# SteppyMk2_10x10.net
KiCad netlist of a schematic drawn in EAGLE
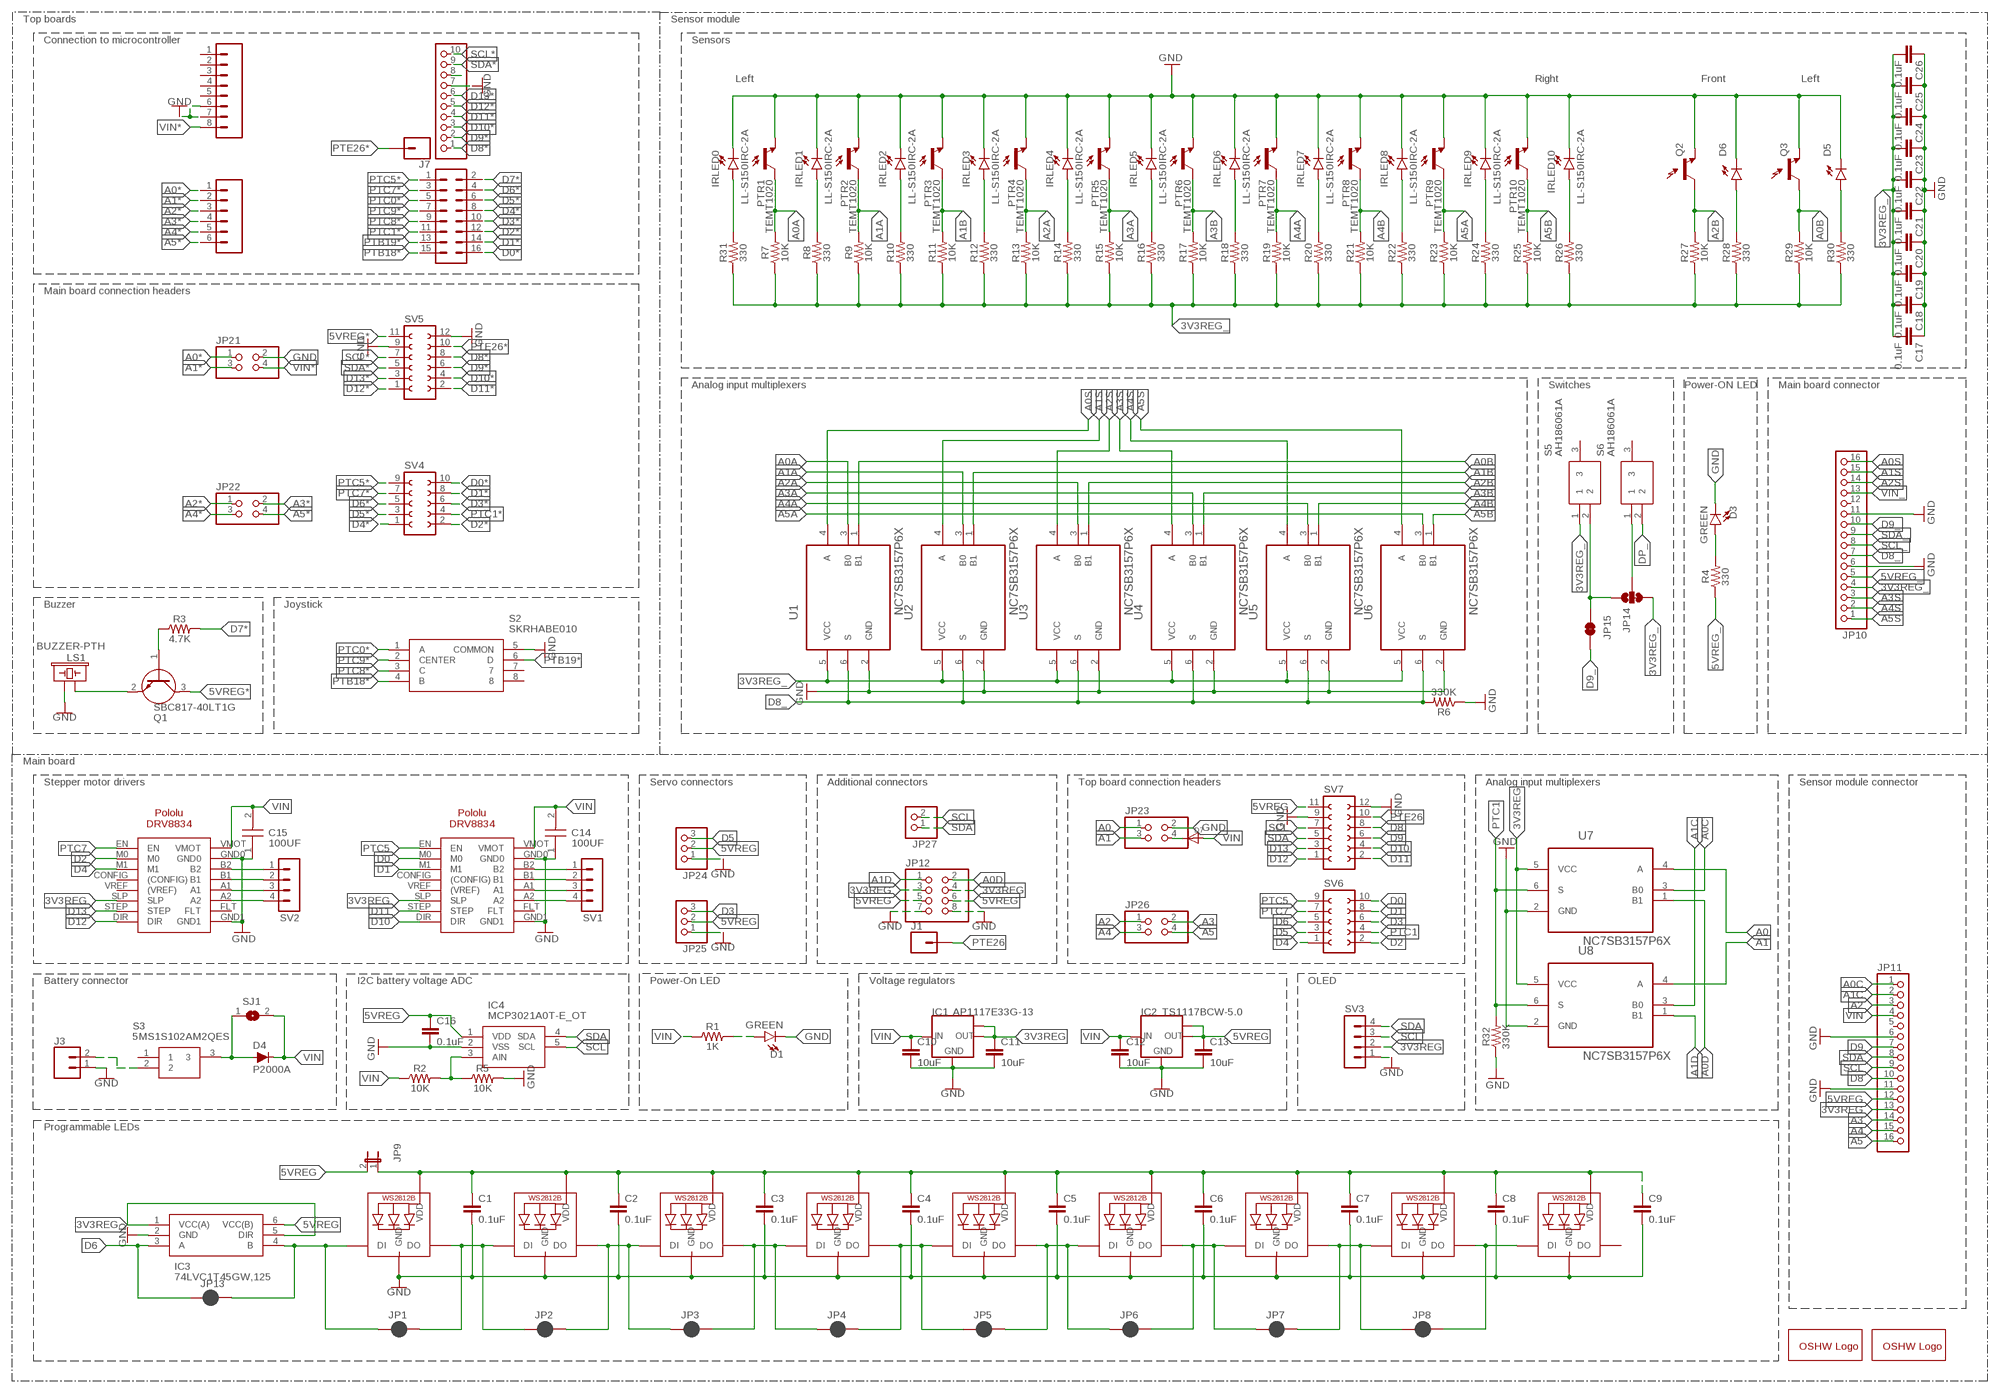
[diagram p0: schematic, sheet 1]

(export (version "E")
  (design (tool "Eeschema 10.0.6"))
  (components
    (comp (ref "C1")
      (value "0.1uF")
      (footprint "eagle-import:0603")
      (libsource (lib "eagle-import") (part "0.1UF-0603-25V-5%"))
    )
    (comp (ref "C2")
      (value "0.1uF")
      (footprint "eagle-import:0603")
      (libsource (lib "eagle-import") (part "0.1UF-0603-25V-5%"))
    )
    (comp (ref "C3")
      (value "0.1uF")
      (footprint "eagle-import:0603")
      (libsource (lib "eagle-import") (part "0.1UF-0603-25V-5%"))
    )
    (comp (ref "C4")
      (value "0.1uF")
      (footprint "eagle-import:0603")
      (libsource (lib "eagle-import") (part "0.1UF-0603-25V-5%"))
    )
    (comp (ref "C5")
      (value "0.1uF")
      (footprint "eagle-import:0603")
      (libsource (lib "eagle-import") (part "0.1UF-0603-25V-5%"))
    )
    (comp (ref "C6")
      (value "0.1uF")
      (footprint "eagle-import:0603")
      (libsource (lib "eagle-import") (part "0.1UF-0603-25V-5%"))
    )
    (comp (ref "C7")
      (value "0.1uF")
      (footprint "eagle-import:0603")
      (libsource (lib "eagle-import") (part "0.1UF-0603-25V-5%"))
    )
    (comp (ref "C8")
      (value "0.1uF")
      (footprint "eagle-import:0603")
      (libsource (lib "eagle-import") (part "0.1UF-0603-25V-5%"))
    )
    (comp (ref "C9")
      (value "0.1uF")
      (footprint "eagle-import:0603")
      (libsource (lib "eagle-import") (part "0.1UF-0603-25V-5%"))
    )
    (comp (ref "C10")
      (value "10uF")
      (footprint "eagle-import:0805")
      (libsource (lib "eagle-import") (part "10UF-0805-10V-10%"))
    )
    (comp (ref "C11")
      (value "10uF")
      (footprint "eagle-import:0805")
      (libsource (lib "eagle-import") (part "10UF-0805-10V-10%"))
    )
    (comp (ref "C12")
      (value "10uF")
      (footprint "eagle-import:0805")
      (libsource (lib "eagle-import") (part "10UF-0805-10V-10%"))
    )
    (comp (ref "C13")
      (value "10uF")
      (footprint "eagle-import:0805")
      (libsource (lib "eagle-import") (part "10UF-0805-10V-10%"))
    )
    (comp (ref "C14")
      (value "100UF")
      (footprint "eagle-import:CAPM7058X610N")
      (fields
        (field (name "MANUFACTURER_PART_NUMBER") "EEEFK1C101P")
        (field (name "RS_PART_NUMBER") "5370433P")
      )
      (libsource (lib "eagle-import") (part "EEEFK1C101P"))
    )
    (comp (ref "C15")
      (value "100UF")
      (footprint "eagle-import:CAPM7058X610N")
      (fields
        (field (name "MANUFACTURER_PART_NUMBER") "EEEFK1C101P")
        (field (name "RS_PART_NUMBER") "5370433P")
      )
      (libsource (lib "eagle-import") (part "EEEFK1C101P"))
    )
    (comp (ref "C16")
      (value "0.1uF")
      (footprint "eagle-import:0603")
      (libsource (lib "eagle-import") (part "0.1UF-0603-25V-5%"))
    )
    (comp (ref "C17")
      (value "0.1uF")
      (footprint "eagle-import:0603")
      (libsource (lib "eagle-import") (part "0.1UF-0603-25V-5%"))
    )
    (comp (ref "C18")
      (value "0.1uF")
      (footprint "eagle-import:0603")
      (libsource (lib "eagle-import") (part "0.1UF-0603-25V-5%"))
    )
    (comp (ref "C19")
      (value "0.1uF")
      (footprint "eagle-import:0603")
      (libsource (lib "eagle-import") (part "0.1UF-0603-25V-5%"))
    )
    (comp (ref "C20")
      (value "0.1uF")
      (footprint "eagle-import:0603")
      (libsource (lib "eagle-import") (part "0.1UF-0603-25V-5%"))
    )
    (comp (ref "C21")
      (value "0.1uF")
      (footprint "eagle-import:0603")
      (libsource (lib "eagle-import") (part "0.1UF-0603-25V-5%"))
    )
    (comp (ref "C22")
      (value "0.1uF")
      (footprint "eagle-import:0603")
      (libsource (lib "eagle-import") (part "0.1UF-0603-25V-5%"))
    )
    (comp (ref "C23")
      (value "0.1uF")
      (footprint "eagle-import:0603")
      (libsource (lib "eagle-import") (part "0.1UF-0603-25V-5%"))
    )
    (comp (ref "C24")
      (value "0.1uF")
      (footprint "eagle-import:0603")
      (libsource (lib "eagle-import") (part "0.1UF-0603-25V-5%"))
    )
    (comp (ref "C25")
      (value "0.1uF")
      (footprint "eagle-import:0603")
      (libsource (lib "eagle-import") (part "0.1UF-0603-25V-5%"))
    )
    (comp (ref "C26")
      (value "0.1uF")
      (footprint "eagle-import:0603")
      (libsource (lib "eagle-import") (part "0.1UF-0603-25V-5%"))
    )
    (comp (ref "CONLEFT")
      (value "POLOLU-DRV8825")
      (footprint "eagle-import:POLOLU-DRV8825")
      (libsource (lib "eagle-import") (part "POLOLU-DRV8825"))
    )
    (comp (ref "D1")
      (value "GREEN")
      (footprint "eagle-import:LED-1206")
      (libsource (lib "eagle-import") (part "LED-GREEN1206"))
    )
    (comp (ref "D3")
      (value "GREEN")
      (footprint "eagle-import:LED-1206")
      (libsource (lib "eagle-import") (part "LED-GREEN1206"))
    )
    (comp (ref "D4")
      (value "P2000A")
      (footprint "eagle-import:DIODE-1N4001")
      (libsource (lib "eagle-import") (part "DIODE-PTH"))
    )
    (comp (ref "D5")
      (value "LED-IRSIDE_EMITTER")
      (footprint "eagle-import:LTE-302")
      (libsource (lib "eagle-import") (part "LED-IRSIDE_EMITTER"))
    )
    (comp (ref "D6")
      (value "LED-IRSIDE_EMITTER")
      (footprint "eagle-import:LTE-302")
      (libsource (lib "eagle-import") (part "LED-IRSIDE_EMITTER"))
    )
    (comp (ref "D7")
      (value "DIODESMA")
      (footprint "eagle-import:SMADIODE")
      (libsource (lib "eagle-import") (part "DIODESMA"))
    )
    (comp (ref "GOLD_ORB_SM1")
      (value "OSHWLOGOLOGO8MM")
      (footprint "eagle-import:OSHW_8MM")
      (libsource (lib "eagle-import") (part "OSHWLOGOLOGO8MM"))
    )
    (comp (ref "GOLD_ORB_SM2")
      (value "OSHWLOGOLOGO5MM")
      (footprint "eagle-import:OSHW_5MM")
      (libsource (lib "eagle-import") (part "OSHWLOGOLOGO5MM"))
    )
    (comp (ref "IC1")
      (value "AP1117E33G-13")
      (footprint "eagle-import:SOT223")
      (libsource (lib "eagle-import") (part "LM1117IMPX-3.3"))
    )
    (comp (ref "IC2")
      (value "TS1117BCW-5.0")
      (footprint "eagle-import:SOT223")
      (libsource (lib "eagle-import") (part "LM1117IMPX-5.0"))
    )
    (comp (ref "IC3")
      (value "74LVC1T45GW,125")
      (footprint "eagle-import:SOT65P210X110-6N")
      (fields
        (field (name "MOUSER_PART_NUMBER") "771-74LVC1T45GW125")
        (field (name "RS_PART_NUMBER") "8168791P")
      )
      (libsource (lib "eagle-import") (part "74LVC1T45GW,125"))
    )
    (comp (ref "IC4")
      (value "MCP3021A0T-E_OT")
      (footprint "eagle-import:SOT95P280X145-5N")
      (fields
        (field (name "MANUFACTURER_PART_NUMBER") "MCP3021A0T-E/OT")
        (field (name "MOUSER_PART_NUMBER") "579-MCP3021A0T-E/OT")
      )
      (libsource (lib "eagle-import") (part "MCP3021A0T-E_OT"))
    )
    (comp (ref "IRLED0")
      (value "LL-S150IRC-2A")
      (footprint "eagle-import:LEDC3215X130N")
      (fields
        (field (name "MANUFACTURER_PART_NUMBER") "PT15-21C/TR8")
        (field (name "MOUSER_PART_NUMBER") "638-PT1521CTR8")
      )
      (libsource (lib "eagle-import") (part "PT15-21C_TR8"))
    )
    (comp (ref "IRLED1")
      (value "LL-S150IRC-2A")
      (footprint "eagle-import:LEDC3215X130N")
      (fields
        (field (name "MANUFACTURER_PART_NUMBER") "PT15-21C/TR8")
        (field (name "MOUSER_PART_NUMBER") "638-PT1521CTR8")
      )
      (libsource (lib "eagle-import") (part "PT15-21C_TR8"))
    )
    (comp (ref "IRLED2")
      (value "LL-S150IRC-2A")
      (footprint "eagle-import:LEDC3215X130N")
      (fields
        (field (name "MANUFACTURER_PART_NUMBER") "PT15-21C/TR8")
        (field (name "MOUSER_PART_NUMBER") "638-PT1521CTR8")
      )
      (libsource (lib "eagle-import") (part "PT15-21C_TR8"))
    )
    (comp (ref "IRLED3")
      (value "LL-S150IRC-2A")
      (footprint "eagle-import:LEDC3215X130N")
      (fields
        (field (name "MANUFACTURER_PART_NUMBER") "PT15-21C/TR8")
        (field (name "MOUSER_PART_NUMBER") "638-PT1521CTR8")
      )
      (libsource (lib "eagle-import") (part "PT15-21C_TR8"))
    )
    (comp (ref "IRLED4")
      (value "LL-S150IRC-2A")
      (footprint "eagle-import:LEDC3215X130N")
      (fields
        (field (name "MANUFACTURER_PART_NUMBER") "PT15-21C/TR8")
        (field (name "MOUSER_PART_NUMBER") "638-PT1521CTR8")
      )
      (libsource (lib "eagle-import") (part "PT15-21C_TR8"))
    )
    (comp (ref "IRLED5")
      (value "LL-S150IRC-2A")
      (footprint "eagle-import:LEDC3215X130N")
      (fields
        (field (name "MANUFACTURER_PART_NUMBER") "PT15-21C/TR8")
        (field (name "MOUSER_PART_NUMBER") "638-PT1521CTR8")
      )
      (libsource (lib "eagle-import") (part "PT15-21C_TR8"))
    )
    (comp (ref "IRLED6")
      (value "LL-S150IRC-2A")
      (footprint "eagle-import:LEDC3215X130N")
      (fields
        (field (name "MANUFACTURER_PART_NUMBER") "PT15-21C/TR8")
        (field (name "MOUSER_PART_NUMBER") "638-PT1521CTR8")
      )
      (libsource (lib "eagle-import") (part "PT15-21C_TR8"))
    )
    (comp (ref "IRLED7")
      (value "LL-S150IRC-2A")
      (footprint "eagle-import:LEDC3215X130N")
      (fields
        (field (name "MANUFACTURER_PART_NUMBER") "PT15-21C/TR8")
        (field (name "MOUSER_PART_NUMBER") "638-PT1521CTR8")
      )
      (libsource (lib "eagle-import") (part "PT15-21C_TR8"))
    )
    (comp (ref "IRLED8")
      (value "LL-S150IRC-2A")
      (footprint "eagle-import:LEDC3215X130N")
      (fields
        (field (name "MANUFACTURER_PART_NUMBER") "PT15-21C/TR8")
        (field (name "MOUSER_PART_NUMBER") "638-PT1521CTR8")
      )
      (libsource (lib "eagle-import") (part "PT15-21C_TR8"))
    )
    (comp (ref "IRLED9")
      (value "LL-S150IRC-2A")
      (footprint "eagle-import:LEDC3215X130N")
      (fields
        (field (name "MANUFACTURER_PART_NUMBER") "PT15-21C/TR8")
        (field (name "MOUSER_PART_NUMBER") "638-PT1521CTR8")
      )
      (libsource (lib "eagle-import") (part "PT15-21C_TR8"))
    )
    (comp (ref "IRLED10")
      (value "LL-S150IRC-2A")
      (footprint "eagle-import:LEDC3215X130N")
      (fields
        (field (name "MANUFACTURER_PART_NUMBER") "PT15-21C/TR8")
        (field (name "MOUSER_PART_NUMBER") "638-PT1521CTR8")
      )
      (libsource (lib "eagle-import") (part "PT15-21C_TR8"))
    )
    (comp (ref "J1")
      (value "CONN_01")
      (footprint "eagle-import:1X01")
      (libsource (lib "eagle-import") (part "CONN_01"))
    )
    (comp (ref "J3")
      (value "CONN_02")
      (footprint "eagle-import:1X02")
      (libsource (lib "eagle-import") (part "CONN_02"))
    )
    (comp (ref "J5")
      (value "CONN_08\"")
      (footprint "eagle-import:1X08")
      (libsource (lib "eagle-import") (part "CONN_08{dblquote}"))
    )
    (comp (ref "J6")
      (value "CONN_06SILK_FEMALE_PTH")
      (footprint "eagle-import:1X06")
      (libsource (lib "eagle-import") (part "CONN_06SILK_FEMALE_PTH"))
    )
    (comp (ref "J7")
      (value "CONN_01")
      (footprint "eagle-import:1X01")
      (libsource (lib "eagle-import") (part "CONN_01"))
    )
    (comp (ref "J8")
      (value "CONN_08X2_HEADER")
      (footprint "eagle-import:2X8")
      (libsource (lib "eagle-import") (part "CONN_08X2_HEADER"))
    )
    (comp (ref "JP1")
      (value "JUMPER-SMT_2_NC_PASTE_SILK")
      (footprint "eagle-import:SMT-JUMPER_2_NC_PASTE_SILK")
      (libsource (lib "eagle-import") (part "JUMPER-SMT_2_NC_PASTE_SILK"))
    )
    (comp (ref "JP2")
      (value "JUMPER-SMT_2_NC_PASTE_SILK")
      (footprint "eagle-import:SMT-JUMPER_2_NC_PASTE_SILK")
      (libsource (lib "eagle-import") (part "JUMPER-SMT_2_NC_PASTE_SILK"))
    )
    (comp (ref "JP3")
      (value "JUMPER-SMT_2_NC_PASTE_SILK")
      (footprint "eagle-import:SMT-JUMPER_2_NC_PASTE_SILK")
      (libsource (lib "eagle-import") (part "JUMPER-SMT_2_NC_PASTE_SILK"))
    )
    (comp (ref "JP4")
      (value "JUMPER-SMT_2_NC_PASTE_SILK")
      (footprint "eagle-import:SMT-JUMPER_2_NC_PASTE_SILK")
      (libsource (lib "eagle-import") (part "JUMPER-SMT_2_NC_PASTE_SILK"))
    )
    (comp (ref "JP5")
      (value "JUMPER-SMT_2_NC_PASTE_SILK")
      (footprint "eagle-import:SMT-JUMPER_2_NC_PASTE_SILK")
      (libsource (lib "eagle-import") (part "JUMPER-SMT_2_NC_PASTE_SILK"))
    )
    (comp (ref "JP6")
      (value "JUMPER-SMT_2_NC_PASTE_SILK")
      (footprint "eagle-import:SMT-JUMPER_2_NC_PASTE_SILK")
      (libsource (lib "eagle-import") (part "JUMPER-SMT_2_NC_PASTE_SILK"))
    )
    (comp (ref "JP7")
      (value "JUMPER-SMT_2_NC_PASTE_SILK")
      (footprint "eagle-import:SMT-JUMPER_2_NC_PASTE_SILK")
      (libsource (lib "eagle-import") (part "JUMPER-SMT_2_NC_PASTE_SILK"))
    )
    (comp (ref "JP8")
      (value "JUMPER-SMT_2_NC_PASTE_SILK")
      (footprint "eagle-import:SMT-JUMPER_2_NC_PASTE_SILK")
      (libsource (lib "eagle-import") (part "JUMPER-SMT_2_NC_PASTE_SILK"))
    )
    (comp (ref "JP9")
      (value "JP1E")
      (footprint "eagle-import:JP1")
      (libsource (lib "eagle-import") (part "JP1E"))
    )
    (comp (ref "JP10")
      (value "PINHD-1X16/90")
      (footprint "eagle-import:1X16_90")
      (libsource (lib "eagle-import") (part "PINHD-1X16/90"))
    )
    (comp (ref "JP11")
      (value "PINHD-1X16")
      (footprint "eagle-import:1X16")
      (libsource (lib "eagle-import") (part "PINHD-1X16"))
    )
    (comp (ref "JP12")
      (value "PINHD-2X4")
      (footprint "eagle-import:2X04")
      (libsource (lib "eagle-import") (part "PINHD-2X4"))
    )
    (comp (ref "JP13")
      (value "JUMPER-SMT_2_NC_PASTE_SILK")
      (footprint "eagle-import:SMT-JUMPER_2_NC_PASTE_SILK")
      (libsource (lib "eagle-import") (part "JUMPER-SMT_2_NC_PASTE_SILK"))
    )
    (comp (ref "JP14")
      (value "JUMPER-SMT_3_1-NC_TRACE_SILK")
      (footprint "eagle-import:SMT-JUMPER_3_1-NC_TRACE_SILK")
      (libsource (lib "eagle-import") (part "JUMPER-SMT_3_1-NC_TRACE_SILK"))
    )
    (comp (ref "JP15")
      (value "JUMPER-SMT_2_NC_TRACE_SILK")
      (footprint "eagle-import:SMT-JUMPER_2_NC_TRACE_SILK")
      (libsource (lib "eagle-import") (part "JUMPER-SMT_2_NC_TRACE_SILK"))
    )
    (comp (ref "JP21")
      (value "PINHD-2X2")
      (footprint "eagle-import:2X02")
      (libsource (lib "eagle-import") (part "PINHD-2X2"))
    )
    (comp (ref "JP22")
      (value "PINHD-2X2")
      (footprint "eagle-import:2X02")
      (libsource (lib "eagle-import") (part "PINHD-2X2"))
    )
    (comp (ref "JP23")
      (value "PINHD-2X2")
      (footprint "eagle-import:2X02")
      (libsource (lib "eagle-import") (part "PINHD-2X2"))
    )
    (comp (ref "JP24")
      (value "PINHD-1X3")
      (footprint "eagle-import:1X03")
      (libsource (lib "eagle-import") (part "PINHD-1X3"))
    )
    (comp (ref "JP25")
      (value "PINHD-1X3")
      (footprint "eagle-import:1X03")
      (libsource (lib "eagle-import") (part "PINHD-1X3"))
    )
    (comp (ref "JP26")
      (value "PINHD-2X2")
      (footprint "eagle-import:2X02")
      (libsource (lib "eagle-import") (part "PINHD-2X2"))
    )
    (comp (ref "JP27")
      (value "PINHD-1X2")
      (footprint "eagle-import:1X02")
      (libsource (lib "eagle-import") (part "PINHD-1X2"))
    )
    (comp (ref "LED1")
      (value "WS2812B3535")
      (footprint "eagle-import:LED3535")
      (libsource (lib "eagle-import") (part "WS2812B3535"))
    )
    (comp (ref "LED2")
      (value "WS2812B3535")
      (footprint "eagle-import:LED3535")
      (libsource (lib "eagle-import") (part "WS2812B3535"))
    )
    (comp (ref "LED3")
      (value "WS2812B3535")
      (footprint "eagle-import:LED3535")
      (libsource (lib "eagle-import") (part "WS2812B3535"))
    )
    (comp (ref "LED4")
      (value "WS2812B3535")
      (footprint "eagle-import:LED3535")
      (libsource (lib "eagle-import") (part "WS2812B3535"))
    )
    (comp (ref "LED5")
      (value "WS2812B3535")
      (footprint "eagle-import:LED3535")
      (libsource (lib "eagle-import") (part "WS2812B3535"))
    )
    (comp (ref "LED6")
      (value "WS2812B3535")
      (footprint "eagle-import:LED3535")
      (libsource (lib "eagle-import") (part "WS2812B3535"))
    )
    (comp (ref "LED7")
      (value "WS2812B3535")
      (footprint "eagle-import:LED3535")
      (libsource (lib "eagle-import") (part "WS2812B3535"))
    )
    (comp (ref "LED8")
      (value "WS2812B3535")
      (footprint "eagle-import:LED3535")
      (libsource (lib "eagle-import") (part "WS2812B3535"))
    )
    (comp (ref "LED9")
      (value "WS2812B3535")
      (footprint "eagle-import:LED3535")
      (libsource (lib "eagle-import") (part "WS2812B3535"))
    )
    (comp (ref "LS1")
      (value "BUZZER-PTH")
      (footprint "eagle-import:BUZZER-12MM")
      (libsource (lib "eagle-import") (part "BUZZER-PTH"))
    )
    (comp (ref "PTR1")
      (value "TEMT1020")
      (footprint "eagle-import:TEMT1020")
      (fields
        (field (name "MANUFACTURER_PART_NUMBER") "TEMD1020")
        (field (name "MOUSER_PART_NUMBER") "782-TEMD1020")
        (field (name "RS_PART_NUMBER") "1808105P")
      )
      (libsource (lib "eagle-import") (part "TEMT1020"))
    )
    (comp (ref "PTR2")
      (value "TEMT1020")
      (footprint "eagle-import:TEMT1020")
      (fields
        (field (name "MANUFACTURER_PART_NUMBER") "TEMD1020")
        (field (name "MOUSER_PART_NUMBER") "782-TEMD1020")
        (field (name "RS_PART_NUMBER") "1808105P")
      )
      (libsource (lib "eagle-import") (part "TEMT1020"))
    )
    (comp (ref "PTR3")
      (value "TEMT1020")
      (footprint "eagle-import:TEMT1020")
      (fields
        (field (name "MANUFACTURER_PART_NUMBER") "TEMD1020")
        (field (name "MOUSER_PART_NUMBER") "782-TEMD1020")
        (field (name "RS_PART_NUMBER") "1808105P")
      )
      (libsource (lib "eagle-import") (part "TEMT1020"))
    )
    (comp (ref "PTR4")
      (value "TEMT1020")
      (footprint "eagle-import:TEMT1020")
      (fields
        (field (name "MANUFACTURER_PART_NUMBER") "TEMD1020")
        (field (name "MOUSER_PART_NUMBER") "782-TEMD1020")
        (field (name "RS_PART_NUMBER") "1808105P")
      )
      (libsource (lib "eagle-import") (part "TEMT1020"))
    )
    (comp (ref "PTR5")
      (value "TEMT1020")
      (footprint "eagle-import:TEMT1020")
      (fields
        (field (name "MANUFACTURER_PART_NUMBER") "TEMD1020")
        (field (name "MOUSER_PART_NUMBER") "782-TEMD1020")
        (field (name "RS_PART_NUMBER") "1808105P")
      )
      (libsource (lib "eagle-import") (part "TEMT1020"))
    )
    (comp (ref "PTR6")
      (value "TEMT1020")
      (footprint "eagle-import:TEMT1020")
      (fields
        (field (name "MANUFACTURER_PART_NUMBER") "TEMD1020")
        (field (name "MOUSER_PART_NUMBER") "782-TEMD1020")
        (field (name "RS_PART_NUMBER") "1808105P")
      )
      (libsource (lib "eagle-import") (part "TEMT1020"))
    )
    (comp (ref "PTR7")
      (value "TEMT1020")
      (footprint "eagle-import:TEMT1020")
      (fields
        (field (name "MANUFACTURER_PART_NUMBER") "TEMD1020")
        (field (name "MOUSER_PART_NUMBER") "782-TEMD1020")
        (field (name "RS_PART_NUMBER") "1808105P")
      )
      (libsource (lib "eagle-import") (part "TEMT1020"))
    )
    (comp (ref "PTR8")
      (value "TEMT1020")
      (footprint "eagle-import:TEMT1020")
      (fields
        (field (name "MANUFACTURER_PART_NUMBER") "TEMD1020")
        (field (name "MOUSER_PART_NUMBER") "782-TEMD1020")
        (field (name "RS_PART_NUMBER") "1808105P")
      )
      (libsource (lib "eagle-import") (part "TEMT1020"))
    )
    (comp (ref "PTR9")
      (value "TEMT1020")
      (footprint "eagle-import:TEMT1020")
      (fields
        (field (name "MANUFACTURER_PART_NUMBER") "TEMD1020")
        (field (name "MOUSER_PART_NUMBER") "782-TEMD1020")
        (field (name "RS_PART_NUMBER") "1808105P")
      )
      (libsource (lib "eagle-import") (part "TEMT1020"))
    )
    (comp (ref "PTR10")
      (value "TEMT1020")
      (footprint "eagle-import:TEMT1020")
      (fields
        (field (name "MANUFACTURER_PART_NUMBER") "TEMD1020")
        (field (name "MOUSER_PART_NUMBER") "782-TEMD1020")
        (field (name "RS_PART_NUMBER") "1808105P")
      )
      (libsource (lib "eagle-import") (part "TEMT1020"))
    )
    (comp (ref "Q1")
      (value "SBC817-40LT1G")
      (footprint "eagle-import:SOT96P237X111-3N")
      (fields
        (field (name "MOUSER_PART_NUMBER") "863-SBC817-40LT1G")
        (field (name "RS_PART_NUMBER") "1631159")
      )
      (libsource (lib "eagle-import") (part "SBC817-40LT1G"))
    )
    (comp (ref "Q2")
      (value "LTR-301")
      (footprint "eagle-import:LTR-301")
      (libsource (lib "eagle-import") (part "LTR-301"))
    )
    (comp (ref "Q3")
      (value "LTR-301")
      (footprint "eagle-import:LTR-301")
      (libsource (lib "eagle-import") (part "LTR-301"))
    )
    (comp (ref "R1")
      (value "1K")
      (footprint "eagle-import:0805")
      (libsource (lib "eagle-import") (part "RESISTOR0805"))
    )
    (comp (ref "R2")
      (value "10K")
      (footprint "eagle-import:0805")
      (libsource (lib "eagle-import") (part "RESISTOR0805"))
    )
    (comp (ref "R3")
      (value "4.7K")
      (footprint "eagle-import:0805")
      (libsource (lib "eagle-import") (part "RESISTOR0805"))
    )
    (comp (ref "R4")
      (value "330")
      (footprint "eagle-import:0805")
      (libsource (lib "eagle-import") (part "RESISTOR0805"))
    )
    (comp (ref "R5")
      (value "10K")
      (footprint "eagle-import:0805")
      (libsource (lib "eagle-import") (part "RESISTOR0805"))
    )
    (comp (ref "R6")
      (value "330K")
      (footprint "eagle-import:0805")
      (libsource (lib "eagle-import") (part "RESISTOR0805"))
    )
    (comp (ref "R7")
      (value "10K")
      (footprint "eagle-import:0805")
      (libsource (lib "eagle-import") (part "RESISTOR0805"))
    )
    (comp (ref "R8")
      (value "330")
      (footprint "eagle-import:0805")
      (libsource (lib "eagle-import") (part "RESISTOR0805"))
    )
    (comp (ref "R9")
      (value "10K")
      (footprint "eagle-import:0805")
      (libsource (lib "eagle-import") (part "RESISTOR0805"))
    )
    (comp (ref "R10")
      (value "330")
      (footprint "eagle-import:0805")
      (libsource (lib "eagle-import") (part "RESISTOR0805"))
    )
    (comp (ref "R11")
      (value "10K")
      (footprint "eagle-import:0805")
      (libsource (lib "eagle-import") (part "RESISTOR0805"))
    )
    (comp (ref "R12")
      (value "330")
      (footprint "eagle-import:0805")
      (libsource (lib "eagle-import") (part "RESISTOR0805"))
    )
    (comp (ref "R13")
      (value "10K")
      (footprint "eagle-import:0805")
      (libsource (lib "eagle-import") (part "RESISTOR0805"))
    )
    (comp (ref "R14")
      (value "330")
      (footprint "eagle-import:0805")
      (libsource (lib "eagle-import") (part "RESISTOR0805"))
    )
    (comp (ref "R15")
      (value "10K")
      (footprint "eagle-import:0805")
      (libsource (lib "eagle-import") (part "RESISTOR0805"))
    )
    (comp (ref "R16")
      (value "330")
      (footprint "eagle-import:0805")
      (libsource (lib "eagle-import") (part "RESISTOR0805"))
    )
    (comp (ref "R17")
      (value "10K")
      (footprint "eagle-import:0805")
      (libsource (lib "eagle-import") (part "RESISTOR0805"))
    )
    (comp (ref "R18")
      (value "330")
      (footprint "eagle-import:0805")
      (libsource (lib "eagle-import") (part "RESISTOR0805"))
    )
    (comp (ref "R19")
      (value "10K")
      (footprint "eagle-import:0805")
      (libsource (lib "eagle-import") (part "RESISTOR0805"))
    )
    (comp (ref "R20")
      (value "330")
      (footprint "eagle-import:0805")
      (libsource (lib "eagle-import") (part "RESISTOR0805"))
    )
    (comp (ref "R21")
      (value "10K")
      (footprint "eagle-import:0805")
      (libsource (lib "eagle-import") (part "RESISTOR0805"))
    )
    (comp (ref "R22")
      (value "330")
      (footprint "eagle-import:0805")
      (libsource (lib "eagle-import") (part "RESISTOR0805"))
    )
    (comp (ref "R23")
      (value "10K")
      (footprint "eagle-import:0805")
      (libsource (lib "eagle-import") (part "RESISTOR0805"))
    )
    (comp (ref "R24")
      (value "330")
      (footprint "eagle-import:0805")
      (libsource (lib "eagle-import") (part "RESISTOR0805"))
    )
    (comp (ref "R25")
      (value "10K")
      (footprint "eagle-import:0805")
      (libsource (lib "eagle-import") (part "RESISTOR0805"))
    )
    (comp (ref "R26")
      (value "330")
      (footprint "eagle-import:0805")
      (libsource (lib "eagle-import") (part "RESISTOR0805"))
    )
    (comp (ref "R27")
      (value "10K")
      (footprint "eagle-import:0805")
      (libsource (lib "eagle-import") (part "RESISTOR0805"))
    )
    (comp (ref "R28")
      (value "330")
      (footprint "eagle-import:0805")
      (libsource (lib "eagle-import") (part "RESISTOR0805"))
    )
    (comp (ref "R29")
      (value "10K")
      (footprint "eagle-import:0805")
      (libsource (lib "eagle-import") (part "RESISTOR0805"))
    )
    (comp (ref "R30")
      (value "330")
      (footprint "eagle-import:0805")
      (libsource (lib "eagle-import") (part "RESISTOR0805"))
    )
    (comp (ref "R31")
      (value "330")
      (footprint "eagle-import:0805")
      (libsource (lib "eagle-import") (part "RESISTOR0805"))
    )
    (comp (ref "R32")
      (value "330K")
      (footprint "eagle-import:0805")
      (libsource (lib "eagle-import") (part "RESISTOR0805"))
    )
    (comp (ref "S2")
      (value "SKRHABE010")
      (footprint "eagle-import:SKRHABE010")
      (fields (field (name "MOUSER_PART_NUMBER") "688-SKRHAB"))
      (libsource (lib "eagle-import") (part "SKRHABE010"))
    )
    (comp (ref "S3")
      (value "5MS1S102AM2QES")
      (footprint "eagle-import:5MS1S102AM2QES")
      (fields (field (name "RS_PART_NUMBER") "7347292"))
      (libsource (lib "eagle-import") (part "5MS1S102AM2QES"))
    )
    (comp (ref "S5")
      (value "AH186061A")
      (footprint "eagle-import:AH186061A")
      (libsource (lib "eagle-import") (part "AH186061A"))
    )
    (comp (ref "S6")
      (value "AH186061A")
      (footprint "eagle-import:AH186061A")
      (libsource (lib "eagle-import") (part "AH186061A"))
    )
    (comp (ref "SJ1")
      (value "SJW")
      (footprint "eagle-import:SJW")
      (libsource (lib "eagle-import") (part "SJW"))
    )
    (comp (ref "SV1")
      (value "MA04-1")
      (footprint "eagle-import:MA04-1")
      (libsource (lib "eagle-import") (part "MA04-1"))
    )
    (comp (ref "SV2")
      (value "MA04-1")
      (footprint "eagle-import:MA04-1")
      (libsource (lib "eagle-import") (part "MA04-1"))
    )
    (comp (ref "SV3")
      (value "MA04-1")
      (footprint "eagle-import:MA04-1")
      (libsource (lib "eagle-import") (part "MA04-1"))
    )
    (comp (ref "SV4")
      (value "FE05-2")
      (footprint "eagle-import:FE05-2")
      (libsource (lib "eagle-import") (part "FE05-2"))
    )
    (comp (ref "SV5")
      (value "FE06-2")
      (footprint "eagle-import:FE06-2")
      (libsource (lib "eagle-import") (part "FE06-2"))
    )
    (comp (ref "SV6")
      (value "FE05-2")
      (footprint "eagle-import:FE05-2")
      (libsource (lib "eagle-import") (part "FE05-2"))
    )
    (comp (ref "SV7")
      (value "FE06-2")
      (footprint "eagle-import:FE06-2")
      (libsource (lib "eagle-import") (part "FE06-2"))
    )
    (comp (ref "U$1")
      (value "PINHD-1X10")
      (footprint "eagle-import:1X10-BIG")
      (libsource (lib "eagle-import") (part "PINHD-1X10"))
    )
    (comp (ref "U$2")
      (value "POLOLU-DRV8825")
      (footprint "eagle-import:POLOLU-DRV8825")
      (libsource (lib "eagle-import") (part "POLOLU-DRV8825"))
    )
    (comp (ref "U1")
      (value "NC7SB3157P6X")
      (footprint "eagle-import:SOT65P210X110-6N")
      (fields (field (name "MF") "ON Semiconductor"))
      (libsource (lib "eagle-import") (part "NC7SB3157P6X"))
    )
    (comp (ref "U2")
      (value "NC7SB3157P6X")
      (footprint "eagle-import:SOT65P210X110-6N")
      (fields (field (name "MF") "ON Semiconductor"))
      (libsource (lib "eagle-import") (part "NC7SB3157P6X"))
    )
    (comp (ref "U3")
      (value "NC7SB3157P6X")
      (footprint "eagle-import:SOT65P210X110-6N")
      (fields (field (name "MF") "ON Semiconductor"))
      (libsource (lib "eagle-import") (part "NC7SB3157P6X"))
    )
    (comp (ref "U4")
      (value "NC7SB3157P6X")
      (footprint "eagle-import:SOT65P210X110-6N")
      (fields (field (name "MF") "ON Semiconductor"))
      (libsource (lib "eagle-import") (part "NC7SB3157P6X"))
    )
    (comp (ref "U5")
      (value "NC7SB3157P6X")
      (footprint "eagle-import:SOT65P210X110-6N")
      (fields (field (name "MF") "ON Semiconductor"))
      (libsource (lib "eagle-import") (part "NC7SB3157P6X"))
    )
    (comp (ref "U6")
      (value "NC7SB3157P6X")
      (footprint "eagle-import:SOT65P210X110-6N")
      (fields (field (name "MF") "ON Semiconductor"))
      (libsource (lib "eagle-import") (part "NC7SB3157P6X"))
    )
    (comp (ref "U7")
      (value "NC7SB3157P6X")
      (footprint "eagle-import:SOT65P210X110-6N")
      (fields (field (name "MF") "ON Semiconductor"))
      (libsource (lib "eagle-import") (part "NC7SB3157P6X"))
    )
    (comp (ref "U8")
      (value "NC7SB3157P6X")
      (footprint "eagle-import:SOT65P210X110-6N")
      (fields (field (name "MF") "ON Semiconductor"))
      (libsource (lib "eagle-import") (part "NC7SB3157P6X"))
    )
  )
  (nets
    (net (code "1") (name "3V3REG") (class "Default")
      (node (ref "C11") (pin "1") (pinfunction "1_1") (pintype "passive"))
      (node (ref "CONLEFT") (pin "SLP") (pinfunction "SLP_SLP") (pintype "bidirectional"))
      (node (ref "IC1") (pin "2") (pinfunction "OUT_2") (pintype "passive"))
      (node (ref "IC1") (pin "TAB") (pinfunction "OUT1_TAB") (pintype "passive"))
      (node (ref "IC3") (pin "1") (pinfunction "VCC(A)_1") (pintype "power_in"))
      (node (ref "IC3") (pin "5") (pinfunction "DIR_5") (pintype "input"))
      (node (ref "JP11") (pin "13") (pinfunction "13_13") (pintype "passive"))
      (node (ref "JP12") (pin "3") (pinfunction "3_3") (pintype "passive"))
      (node (ref "JP12") (pin "4") (pinfunction "4_4") (pintype "passive"))
      (node (ref "SV3") (pin "2") (pinfunction "2_2") (pintype "passive"))
      (node (ref "U$2") (pin "SLP") (pinfunction "SLP_SLP") (pintype "bidirectional"))
      (node (ref "U7") (pin "5") (pinfunction "VCC_5") (pintype "power_in"))
      (node (ref "U8") (pin "5") (pinfunction "VCC_5") (pintype "power_in"))
    )
    (net (code "2") (name "3V3REG_") (class "Default")
      (node (ref "C17") (pin "2") (pinfunction "2_2") (pintype "passive"))
      (node (ref "C18") (pin "2") (pinfunction "2_2") (pintype "passive"))
      (node (ref "C19") (pin "2") (pinfunction "2_2") (pintype "passive"))
      (node (ref "C20") (pin "2") (pinfunction "2_2") (pintype "passive"))
      (node (ref "C21") (pin "2") (pinfunction "2_2") (pintype "passive"))
      (node (ref "C22") (pin "2") (pinfunction "2_2") (pintype "passive"))
      (node (ref "C23") (pin "2") (pinfunction "2_2") (pintype "passive"))
      (node (ref "C24") (pin "2") (pinfunction "2_2") (pintype "passive"))
      (node (ref "C25") (pin "2") (pinfunction "2_2") (pintype "passive"))
      (node (ref "C26") (pin "2") (pinfunction "2_2") (pintype "passive"))
      (node (ref "JP10") (pin "4") (pinfunction "4_4") (pintype "passive"))
      (node (ref "JP14") (pin "3") (pinfunction "3_3") (pintype "passive"))
      (node (ref "R10") (pin "1") (pinfunction "1_1") (pintype "passive"))
      (node (ref "R11") (pin "1") (pinfunction "1_1") (pintype "passive"))
      (node (ref "R12") (pin "1") (pinfunction "1_1") (pintype "passive"))
      (node (ref "R13") (pin "1") (pinfunction "1_1") (pintype "passive"))
      (node (ref "R14") (pin "1") (pinfunction "1_1") (pintype "passive"))
      (node (ref "R15") (pin "1") (pinfunction "1_1") (pintype "passive"))
      (node (ref "R16") (pin "1") (pinfunction "1_1") (pintype "passive"))
      (node (ref "R17") (pin "1") (pinfunction "1_1") (pintype "passive"))
      (node (ref "R18") (pin "1") (pinfunction "1_1") (pintype "passive"))
      (node (ref "R19") (pin "1") (pinfunction "1_1") (pintype "passive"))
      (node (ref "R20") (pin "1") (pinfunction "1_1") (pintype "passive"))
      (node (ref "R21") (pin "1") (pinfunction "1_1") (pintype "passive"))
      (node (ref "R22") (pin "1") (pinfunction "1_1") (pintype "passive"))
      (node (ref "R23") (pin "1") (pinfunction "1_1") (pintype "passive"))
      (node (ref "R24") (pin "1") (pinfunction "1_1") (pintype "passive"))
      (node (ref "R25") (pin "1") (pinfunction "1_1") (pintype "passive"))
      (node (ref "R26") (pin "1") (pinfunction "1_1") (pintype "passive"))
      (node (ref "R27") (pin "1") (pinfunction "1_1") (pintype "passive"))
      (node (ref "R28") (pin "1") (pinfunction "1_1") (pintype "passive"))
      (node (ref "R29") (pin "1") (pinfunction "1_1") (pintype "passive"))
      (node (ref "R30") (pin "1") (pinfunction "1_1") (pintype "passive"))
      (node (ref "R31") (pin "1") (pinfunction "1_1") (pintype "passive"))
      (node (ref "R7") (pin "1") (pinfunction "1_1") (pintype "passive"))
      (node (ref "R8") (pin "1") (pinfunction "1_1") (pintype "passive"))
      (node (ref "R9") (pin "1") (pinfunction "1_1") (pintype "passive"))
      (node (ref "S5") (pin "1") (pinfunction "1_1") (pintype "bidirectional"))
      (node (ref "U1") (pin "5") (pinfunction "VCC_5") (pintype "power_in"))
      (node (ref "U2") (pin "5") (pinfunction "VCC_5") (pintype "power_in"))
      (node (ref "U3") (pin "5") (pinfunction "VCC_5") (pintype "power_in"))
      (node (ref "U4") (pin "5") (pinfunction "VCC_5") (pintype "power_in"))
      (node (ref "U5") (pin "5") (pinfunction "VCC_5") (pintype "power_in"))
      (node (ref "U6") (pin "5") (pinfunction "VCC_5") (pintype "power_in"))
    )
    (net (code "3") (name "5VREG") (class "Default")
      (node (ref "C13") (pin "1") (pinfunction "1_1") (pintype "passive"))
      (node (ref "C16") (pin "1") (pinfunction "1_1") (pintype "passive"))
      (node (ref "IC2") (pin "2") (pinfunction "OUT_2") (pintype "passive"))
      (node (ref "IC2") (pin "TAB") (pinfunction "OUT1_TAB") (pintype "passive"))
      (node (ref "IC3") (pin "6") (pinfunction "VCC(B)_6") (pintype "power_in"))
      (node (ref "IC4") (pin "1") (pinfunction "VDD_1") (pintype "bidirectional"))
      (node (ref "JP11") (pin "12") (pinfunction "12_12") (pintype "passive"))
      (node (ref "JP12") (pin "5") (pinfunction "5_5") (pintype "passive"))
      (node (ref "JP12") (pin "6") (pinfunction "6_6") (pintype "passive"))
      (node (ref "JP24") (pin "2") (pinfunction "2_2") (pintype "passive"))
      (node (ref "JP25") (pin "2") (pinfunction "2_2") (pintype "passive"))
      (node (ref "JP9") (pin "2") (pinfunction "2_2") (pintype "passive"))
      (node (ref "SV7") (pin "11") (pinfunction "11_11") (pintype "passive"))
    )
    (net (code "4") (name "5VREG*") (class "Default")
      (node (ref "Q1") (pin "3") (pinfunction "C_3") (pintype "bidirectional"))
      (node (ref "SV5") (pin "11") (pinfunction "11_11") (pintype "passive"))
    )
    (net (code "5") (name "5VREG_") (class "Default")
      (node (ref "JP10") (pin "5") (pinfunction "5_5") (pintype "passive"))
      (node (ref "R4") (pin "1") (pinfunction "1_1") (pintype "passive"))
    )
    (net (code "6") (name "A0") (class "Default")
      (node (ref "JP23") (pin "1") (pinfunction "1_1") (pintype "passive"))
      (node (ref "U7") (pin "4") (pinfunction "A_4") (pintype "passive"))
    )
    (net (code "7") (name "A0*") (class "Default")
      (node (ref "J6") (pin "1") (pinfunction "1_1") (pintype "passive"))
      (node (ref "JP21") (pin "1") (pinfunction "1_1") (pintype "passive"))
    )
    (net (code "8") (name "A0A") (class "Default")
      (node (ref "PTR1") (pin "1") (pinfunction "C_1") (pintype "passive"))
      (node (ref "R7") (pin "2") (pinfunction "2_2") (pintype "passive"))
      (node (ref "U1") (pin "3") (pinfunction "B0_3") (pintype "passive"))
    )
    (net (code "9") (name "A0B") (class "Default")
      (node (ref "Q3") (pin "C") (pinfunction "C1_C") (pintype "passive"))
      (node (ref "R29") (pin "2") (pinfunction "2_2") (pintype "passive"))
      (node (ref "U1") (pin "1") (pinfunction "B1_1") (pintype "passive"))
    )
    (net (code "10") (name "A0C") (class "Default")
      (node (ref "JP11") (pin "1") (pinfunction "1_1") (pintype "passive"))
      (node (ref "U7") (pin "3") (pinfunction "B0_3") (pintype "passive"))
    )
    (net (code "11") (name "A0D") (class "Default")
      (node (ref "JP12") (pin "2") (pinfunction "2_2") (pintype "passive"))
      (node (ref "U7") (pin "1") (pinfunction "B1_1") (pintype "passive"))
    )
    (net (code "12") (name "A0S") (class "Default")
      (node (ref "JP10") (pin "16") (pinfunction "16_16") (pintype "passive"))
      (node (ref "U1") (pin "4") (pinfunction "A_4") (pintype "passive"))
    )
    (net (code "13") (name "A1") (class "Default")
      (node (ref "JP23") (pin "3") (pinfunction "3_3") (pintype "passive"))
      (node (ref "U8") (pin "4") (pinfunction "A_4") (pintype "passive"))
    )
    (net (code "14") (name "A1*") (class "Default")
      (node (ref "J6") (pin "2") (pinfunction "2_2") (pintype "passive"))
      (node (ref "JP21") (pin "3") (pinfunction "3_3") (pintype "passive"))
    )
    (net (code "15") (name "A1A") (class "Default")
      (node (ref "PTR2") (pin "1") (pinfunction "C_1") (pintype "passive"))
      (node (ref "R9") (pin "2") (pinfunction "2_2") (pintype "passive"))
      (node (ref "U2") (pin "3") (pinfunction "B0_3") (pintype "passive"))
    )
    (net (code "16") (name "A1B") (class "Default")
      (node (ref "PTR3") (pin "1") (pinfunction "C_1") (pintype "passive"))
      (node (ref "R11") (pin "2") (pinfunction "2_2") (pintype "passive"))
      (node (ref "U2") (pin "1") (pinfunction "B1_1") (pintype "passive"))
    )
    (net (code "17") (name "A1C") (class "Default")
      (node (ref "JP11") (pin "2") (pinfunction "2_2") (pintype "passive"))
      (node (ref "U8") (pin "3") (pinfunction "B0_3") (pintype "passive"))
    )
    (net (code "18") (name "A1D") (class "Default")
      (node (ref "JP12") (pin "1") (pinfunction "1_1") (pintype "passive"))
      (node (ref "U8") (pin "1") (pinfunction "B1_1") (pintype "passive"))
    )
    (net (code "19") (name "A1S") (class "Default")
      (node (ref "JP10") (pin "15") (pinfunction "15_15") (pintype "passive"))
      (node (ref "U2") (pin "4") (pinfunction "A_4") (pintype "passive"))
    )
    (net (code "20") (name "A2") (class "Default")
      (node (ref "JP11") (pin "3") (pinfunction "3_3") (pintype "passive"))
      (node (ref "JP26") (pin "1") (pinfunction "1_1") (pintype "passive"))
    )
    (net (code "21") (name "A2*") (class "Default")
      (node (ref "J6") (pin "3") (pinfunction "3_3") (pintype "passive"))
      (node (ref "JP22") (pin "1") (pinfunction "1_1") (pintype "passive"))
    )
    (net (code "22") (name "A2A") (class "Default")
      (node (ref "PTR4") (pin "1") (pinfunction "C_1") (pintype "passive"))
      (node (ref "R13") (pin "2") (pinfunction "2_2") (pintype "passive"))
      (node (ref "U3") (pin "3") (pinfunction "B0_3") (pintype "passive"))
    )
    (net (code "23") (name "A2B") (class "Default")
      (node (ref "Q2") (pin "C") (pinfunction "C1_C") (pintype "passive"))
      (node (ref "R27") (pin "2") (pinfunction "2_2") (pintype "passive"))
      (node (ref "U3") (pin "1") (pinfunction "B1_1") (pintype "passive"))
    )
    (net (code "24") (name "A2S") (class "Default")
      (node (ref "JP10") (pin "14") (pinfunction "14_14") (pintype "passive"))
      (node (ref "U3") (pin "4") (pinfunction "A_4") (pintype "passive"))
    )
    (net (code "25") (name "A3") (class "Default")
      (node (ref "JP11") (pin "14") (pinfunction "14_14") (pintype "passive"))
      (node (ref "JP26") (pin "2") (pinfunction "2_2") (pintype "passive"))
    )
    (net (code "26") (name "A3*") (class "Default")
      (node (ref "J6") (pin "4") (pinfunction "4_4") (pintype "passive"))
      (node (ref "JP22") (pin "2") (pinfunction "2_2") (pintype "passive"))
    )
    (net (code "27") (name "A3A") (class "Default")
      (node (ref "PTR5") (pin "1") (pinfunction "C_1") (pintype "passive"))
      (node (ref "R15") (pin "2") (pinfunction "2_2") (pintype "passive"))
      (node (ref "U4") (pin "3") (pinfunction "B0_3") (pintype "passive"))
    )
    (net (code "28") (name "A3B") (class "Default")
      (node (ref "PTR6") (pin "1") (pinfunction "C_1") (pintype "passive"))
      (node (ref "R17") (pin "2") (pinfunction "2_2") (pintype "passive"))
      (node (ref "U4") (pin "1") (pinfunction "B1_1") (pintype "passive"))
    )
    (net (code "29") (name "A3S") (class "Default")
      (node (ref "JP10") (pin "3") (pinfunction "3_3") (pintype "passive"))
      (node (ref "U4") (pin "4") (pinfunction "A_4") (pintype "passive"))
    )
    (net (code "30") (name "A4") (class "Default")
      (node (ref "JP11") (pin "15") (pinfunction "15_15") (pintype "passive"))
      (node (ref "JP26") (pin "3") (pinfunction "3_3") (pintype "passive"))
    )
    (net (code "31") (name "A4*") (class "Default")
      (node (ref "J6") (pin "5") (pinfunction "5_5") (pintype "passive"))
      (node (ref "JP22") (pin "3") (pinfunction "3_3") (pintype "passive"))
    )
    (net (code "32") (name "A4A") (class "Default")
      (node (ref "PTR7") (pin "1") (pinfunction "C_1") (pintype "passive"))
      (node (ref "R19") (pin "2") (pinfunction "2_2") (pintype "passive"))
      (node (ref "U5") (pin "3") (pinfunction "B0_3") (pintype "passive"))
    )
    (net (code "33") (name "A4B") (class "Default")
      (node (ref "PTR8") (pin "1") (pinfunction "C_1") (pintype "passive"))
      (node (ref "R21") (pin "2") (pinfunction "2_2") (pintype "passive"))
      (node (ref "U5") (pin "1") (pinfunction "B1_1") (pintype "passive"))
    )
    (net (code "34") (name "A4S") (class "Default")
      (node (ref "JP10") (pin "2") (pinfunction "2_2") (pintype "passive"))
      (node (ref "U5") (pin "4") (pinfunction "A_4") (pintype "passive"))
    )
    (net (code "35") (name "A5") (class "Default")
      (node (ref "JP11") (pin "16") (pinfunction "16_16") (pintype "passive"))
      (node (ref "JP26") (pin "4") (pinfunction "4_4") (pintype "passive"))
    )
    (net (code "36") (name "A5*") (class "Default")
      (node (ref "J6") (pin "6") (pinfunction "6_6") (pintype "passive"))
      (node (ref "JP22") (pin "4") (pinfunction "4_4") (pintype "passive"))
    )
    (net (code "37") (name "A5A") (class "Default")
      (node (ref "PTR9") (pin "1") (pinfunction "C_1") (pintype "passive"))
      (node (ref "R23") (pin "2") (pinfunction "2_2") (pintype "passive"))
      (node (ref "U6") (pin "3") (pinfunction "B0_3") (pintype "passive"))
    )
    (net (code "38") (name "A5B") (class "Default")
      (node (ref "PTR10") (pin "1") (pinfunction "C_1") (pintype "passive"))
      (node (ref "R25") (pin "2") (pinfunction "2_2") (pintype "passive"))
      (node (ref "U6") (pin "1") (pinfunction "B1_1") (pintype "passive"))
    )
    (net (code "39") (name "A5S") (class "Default")
      (node (ref "JP10") (pin "1") (pinfunction "1_1") (pintype "passive"))
      (node (ref "U6") (pin "4") (pinfunction "A_4") (pintype "passive"))
    )
    (net (code "40") (name "D0") (class "Default")
      (node (ref "SV6") (pin "10") (pinfunction "10_10") (pintype "passive"))
      (node (ref "U$2") (pin "M0") (pinfunction "M0_M0") (pintype "bidirectional"))
    )
    (net (code "41") (name "D0*") (class "Default")
      (node (ref "J8") (pin "16") (pinfunction "16_16") (pintype "passive"))
      (node (ref "SV4") (pin "10") (pinfunction "10_10") (pintype "passive"))
    )
    (net (code "42") (name "D1") (class "Default")
      (node (ref "SV6") (pin "8") (pinfunction "8_8") (pintype "passive"))
      (node (ref "U$2") (pin "M1") (pinfunction "M1_M1") (pintype "bidirectional"))
    )
    (net (code "43") (name "D1*") (class "Default")
      (node (ref "J8") (pin "14") (pinfunction "14_14") (pintype "passive"))
      (node (ref "SV4") (pin "8") (pinfunction "8_8") (pintype "passive"))
    )
    (net (code "44") (name "D2") (class "Default")
      (node (ref "CONLEFT") (pin "M0") (pinfunction "M0_M0") (pintype "bidirectional"))
      (node (ref "SV6") (pin "2") (pinfunction "2_2") (pintype "passive"))
    )
    (net (code "45") (name "D2*") (class "Default")
      (node (ref "J8") (pin "12") (pinfunction "12_12") (pintype "passive"))
      (node (ref "SV4") (pin "2") (pinfunction "2_2") (pintype "passive"))
    )
    (net (code "46") (name "D3") (class "Default")
      (node (ref "JP25") (pin "3") (pinfunction "3_3") (pintype "passive"))
      (node (ref "SV6") (pin "6") (pinfunction "6_6") (pintype "passive"))
    )
    (net (code "47") (name "D3*") (class "Default")
      (node (ref "J8") (pin "10") (pinfunction "10_10") (pintype "passive"))
      (node (ref "SV4") (pin "6") (pinfunction "6_6") (pintype "passive"))
    )
    (net (code "48") (name "D4") (class "Default")
      (node (ref "CONLEFT") (pin "M1") (pinfunction "M1_M1") (pintype "bidirectional"))
      (node (ref "SV6") (pin "1") (pinfunction "1_1") (pintype "passive"))
    )
    (net (code "49") (name "D4*") (class "Default")
      (node (ref "J8") (pin "8") (pinfunction "8_8") (pintype "passive"))
      (node (ref "SV4") (pin "1") (pinfunction "1_1") (pintype "passive"))
    )
    (net (code "50") (name "D5") (class "Default")
      (node (ref "JP24") (pin "3") (pinfunction "3_3") (pintype "passive"))
      (node (ref "SV6") (pin "3") (pinfunction "3_3") (pintype "passive"))
    )
    (net (code "51") (name "D5*") (class "Default")
      (node (ref "J8") (pin "6") (pinfunction "6_6") (pintype "passive"))
      (node (ref "SV4") (pin "3") (pinfunction "3_3") (pintype "passive"))
    )
    (net (code "52") (name "D6") (class "Default")
      (node (ref "IC3") (pin "3") (pinfunction "A_3") (pintype "bidirectional"))
      (node (ref "JP13") (pin "1") (pinfunction "1_1") (pintype "passive"))
      (node (ref "SV6") (pin "5") (pinfunction "5_5") (pintype "passive"))
    )
    (net (code "53") (name "D6*") (class "Default")
      (node (ref "J8") (pin "4") (pinfunction "4_4") (pintype "passive"))
      (node (ref "SV4") (pin "5") (pinfunction "5_5") (pintype "passive"))
    )
    (net (code "54") (name "D7*") (class "Default")
      (node (ref "J8") (pin "2") (pinfunction "2_2") (pintype "passive"))
      (node (ref "R3") (pin "2") (pinfunction "2_2") (pintype "passive"))
    )
    (net (code "55") (name "D8") (class "Default")
      (node (ref "JP11") (pin "10") (pinfunction "10_10") (pintype "passive"))
      (node (ref "SV7") (pin "8") (pinfunction "8_8") (pintype "passive"))
    )
    (net (code "56") (name "D8*") (class "Default")
      (node (ref "SV5") (pin "8") (pinfunction "8_8") (pintype "passive"))
      (node (ref "U$1") (pin "1") (pinfunction "1_1") (pintype "passive"))
    )
    (net (code "57") (name "D8_") (class "Default")
      (node (ref "JP10") (pin "7") (pinfunction "7_7") (pintype "passive"))
      (node (ref "R6") (pin "2") (pinfunction "2_2") (pintype "passive"))
      (node (ref "U1") (pin "6") (pinfunction "S_6") (pintype "input"))
      (node (ref "U2") (pin "6") (pinfunction "S_6") (pintype "input"))
      (node (ref "U3") (pin "6") (pinfunction "S_6") (pintype "input"))
      (node (ref "U4") (pin "6") (pinfunction "S_6") (pintype "input"))
      (node (ref "U5") (pin "6") (pinfunction "S_6") (pintype "input"))
      (node (ref "U6") (pin "6") (pinfunction "S_6") (pintype "input"))
    )
    (net (code "58") (name "D9") (class "Default")
      (node (ref "JP11") (pin "7") (pinfunction "7_7") (pintype "passive"))
      (node (ref "SV7") (pin "6") (pinfunction "6_6") (pintype "passive"))
    )
    (net (code "59") (name "D9*") (class "Default")
      (node (ref "SV5") (pin "6") (pinfunction "6_6") (pintype "passive"))
      (node (ref "U$1") (pin "2") (pinfunction "2_2") (pintype "passive"))
    )
    (net (code "60") (name "D9_") (class "Default")
      (node (ref "JP10") (pin "10") (pinfunction "10_10") (pintype "passive"))
      (node (ref "JP15") (pin "1") (pinfunction "1_1") (pintype "passive"))
    )
    (net (code "61") (name "D10") (class "Default")
      (node (ref "SV7") (pin "4") (pinfunction "4_4") (pintype "passive"))
      (node (ref "U$2") (pin "DIR") (pinfunction "DIR_DIR") (pintype "bidirectional"))
    )
    (net (code "62") (name "D10*") (class "Default")
      (node (ref "SV5") (pin "4") (pinfunction "4_4") (pintype "passive"))
      (node (ref "U$1") (pin "3") (pinfunction "3_3") (pintype "passive"))
    )
    (net (code "63") (name "D11") (class "Default")
      (node (ref "SV7") (pin "2") (pinfunction "2_2") (pintype "passive"))
      (node (ref "U$2") (pin "STEP") (pinfunction "STEP_STEP") (pintype "bidirectional"))
    )
    (net (code "64") (name "D11*") (class "Default")
      (node (ref "SV5") (pin "2") (pinfunction "2_2") (pintype "passive"))
      (node (ref "U$1") (pin "4") (pinfunction "4_4") (pintype "passive"))
    )
    (net (code "65") (name "D12") (class "Default")
      (node (ref "CONLEFT") (pin "DIR") (pinfunction "DIR_DIR") (pintype "bidirectional"))
      (node (ref "SV7") (pin "1") (pinfunction "1_1") (pintype "passive"))
    )
    (net (code "66") (name "D12*") (class "Default")
      (node (ref "SV5") (pin "1") (pinfunction "1_1") (pintype "passive"))
      (node (ref "U$1") (pin "5") (pinfunction "5_5") (pintype "passive"))
    )
    (net (code "67") (name "D13") (class "Default")
      (node (ref "CONLEFT") (pin "STEP") (pinfunction "STEP_STEP") (pintype "bidirectional"))
      (node (ref "SV7") (pin "3") (pinfunction "3_3") (pintype "passive"))
    )
    (net (code "68") (name "D13*") (class "Default")
      (node (ref "SV5") (pin "3") (pinfunction "3_3") (pintype "passive"))
      (node (ref "U$1") (pin "6") (pinfunction "6_6") (pintype "passive"))
    )
    (net (code "69") (name "DP_") (class "Default")
      (node (ref "S6") (pin "2") (pinfunction "2_2") (pintype "bidirectional"))
    )
    (net (code "70") (name "GND") (class "Default")
      (node (ref "C1") (pin "2") (pinfunction "2_2") (pintype "passive"))
      (node (ref "C10") (pin "2") (pinfunction "2_2") (pintype "passive"))
      (node (ref "C11") (pin "2") (pinfunction "2_2") (pintype "passive"))
      (node (ref "C12") (pin "2") (pinfunction "2_2") (pintype "passive"))
      (node (ref "C13") (pin "2") (pinfunction "2_2") (pintype "passive"))
      (node (ref "C14") (pin "1") (pinfunction "1_1") (pintype "bidirectional"))
      (node (ref "C15") (pin "1") (pinfunction "1_1") (pintype "bidirectional"))
      (node (ref "C16") (pin "2") (pinfunction "2_2") (pintype "passive"))
      (node (ref "C17") (pin "1") (pinfunction "1_1") (pintype "passive"))
      (node (ref "C18") (pin "1") (pinfunction "1_1") (pintype "passive"))
      (node (ref "C19") (pin "1") (pinfunction "1_1") (pintype "passive"))
      (node (ref "C2") (pin "2") (pinfunction "2_2") (pintype "passive"))
      (node (ref "C20") (pin "1") (pinfunction "1_1") (pintype "passive"))
      (node (ref "C21") (pin "1") (pinfunction "1_1") (pintype "passive"))
      (node (ref "C22") (pin "1") (pinfunction "1_1") (pintype "passive"))
      (node (ref "C23") (pin "1") (pinfunction "1_1") (pintype "passive"))
      (node (ref "C24") (pin "1") (pinfunction "1_1") (pintype "passive"))
      (node (ref "C25") (pin "1") (pinfunction "1_1") (pintype "passive"))
      (node (ref "C26") (pin "1") (pinfunction "1_1") (pintype "passive"))
      (node (ref "C3") (pin "2") (pinfunction "2_2") (pintype "passive"))
      (node (ref "C4") (pin "2") (pinfunction "2_2") (pintype "passive"))
      (node (ref "C5") (pin "2") (pinfunction "2_2") (pintype "passive"))
      (node (ref "C6") (pin "2") (pinfunction "2_2") (pintype "passive"))
      (node (ref "C7") (pin "2") (pinfunction "2_2") (pintype "passive"))
      (node (ref "C8") (pin "2") (pinfunction "2_2") (pintype "passive"))
      (node (ref "C9") (pin "2") (pinfunction "2_2") (pintype "passive"))
      (node (ref "CONLEFT") (pin "GND0") (pinfunction "GND0_GND0") (pintype "bidirectional"))
      (node (ref "CONLEFT") (pin "GND1") (pinfunction "GND1_GND1") (pintype "bidirectional"))
      (node (ref "D1") (pin "C") (pinfunction "C_C") (pintype "passive"))
      (node (ref "D3") (pin "C") (pinfunction "C_C") (pintype "passive"))
      (node (ref "D5") (pin "C") (pinfunction "C_C") (pintype "passive"))
      (node (ref "D6") (pin "C") (pinfunction "C_C") (pintype "passive"))
      (node (ref "IC1") (pin "1") (pinfunction "GND_1") (pintype "input"))
      (node (ref "IC2") (pin "1") (pinfunction "GND_1") (pintype "input"))
      (node (ref "IC3") (pin "2") (pinfunction "GND_2") (pintype "power_in"))
      (node (ref "IC4") (pin "2") (pinfunction "VSS_2") (pintype "bidirectional"))
      (node (ref "IRLED0") (pin "2") (pinfunction "C_2") (pintype "passive"))
      (node (ref "IRLED1") (pin "2") (pinfunction "C_2") (pintype "passive"))
      (node (ref "IRLED10") (pin "2") (pinfunction "C_2") (pintype "passive"))
      (node (ref "IRLED2") (pin "2") (pinfunction "C_2") (pintype "passive"))
      (node (ref "IRLED3") (pin "2") (pinfunction "C_2") (pintype "passive"))
      (node (ref "IRLED4") (pin "2") (pinfunction "C_2") (pintype "passive"))
      (node (ref "IRLED5") (pin "2") (pinfunction "C_2") (pintype "passive"))
      (node (ref "IRLED6") (pin "2") (pinfunction "C_2") (pintype "passive"))
      (node (ref "IRLED7") (pin "2") (pinfunction "C_2") (pintype "passive"))
      (node (ref "IRLED8") (pin "2") (pinfunction "C_2") (pintype "passive"))
      (node (ref "IRLED9") (pin "2") (pinfunction "C_2") (pintype "passive"))
      (node (ref "J3") (pin "1") (pinfunction "1_1") (pintype "passive"))
      (node (ref "J5") (pin "6") (pinfunction "6_6") (pintype "passive"))
      (node (ref "J5") (pin "7") (pinfunction "7_7") (pintype "passive"))
      (node (ref "JP10") (pin "11") (pinfunction "11_11") (pintype "passive"))
      (node (ref "JP10") (pin "6") (pinfunction "6_6") (pintype "passive"))
      (node (ref "JP11") (pin "11") (pinfunction "11_11") (pintype "passive"))
      (node (ref "JP11") (pin "6") (pinfunction "6_6") (pintype "passive"))
      (node (ref "JP12") (pin "7") (pinfunction "7_7") (pintype "passive"))
      (node (ref "JP12") (pin "8") (pinfunction "8_8") (pintype "passive"))
      (node (ref "JP21") (pin "2") (pinfunction "2_2") (pintype "passive"))
      (node (ref "JP23") (pin "2") (pinfunction "2_2") (pintype "passive"))
      (node (ref "JP24") (pin "1") (pinfunction "1_1") (pintype "passive"))
      (node (ref "JP25") (pin "1") (pinfunction "1_1") (pintype "passive"))
      (node (ref "LED1") (pin "4") (pinfunction "GND_4") (pintype "power_in"))
      (node (ref "LED2") (pin "4") (pinfunction "GND_4") (pintype "power_in"))
      (node (ref "LED3") (pin "4") (pinfunction "GND_4") (pintype "power_in"))
      (node (ref "LED4") (pin "4") (pinfunction "GND_4") (pintype "power_in"))
      (node (ref "LED5") (pin "4") (pinfunction "GND_4") (pintype "power_in"))
      (node (ref "LED6") (pin "4") (pinfunction "GND_4") (pintype "power_in"))
      (node (ref "LED7") (pin "4") (pinfunction "GND_4") (pintype "power_in"))
      (node (ref "LED8") (pin "4") (pinfunction "GND_4") (pintype "power_in"))
      (node (ref "LED9") (pin "4") (pinfunction "GND_4") (pintype "power_in"))
      (node (ref "LS1") (pin "-") (pinfunction "2_-") (pintype "passive"))
      (node (ref "PTR1") (pin "2") (pinfunction "E_2") (pintype "passive"))
      (node (ref "PTR10") (pin "2") (pinfunction "E_2") (pintype "passive"))
      (node (ref "PTR2") (pin "2") (pinfunction "E_2") (pintype "passive"))
      (node (ref "PTR3") (pin "2") (pinfunction "E_2") (pintype "passive"))
      (node (ref "PTR4") (pin "2") (pinfunction "E_2") (pintype "passive"))
      (node (ref "PTR5") (pin "2") (pinfunction "E_2") (pintype "passive"))
      (node (ref "PTR6") (pin "2") (pinfunction "E_2") (pintype "passive"))
      (node (ref "PTR7") (pin "2") (pinfunction "E_2") (pintype "passive"))
      (node (ref "PTR8") (pin "2") (pinfunction "E_2") (pintype "passive"))
      (node (ref "PTR9") (pin "2") (pinfunction "E_2") (pintype "passive"))
      (node (ref "Q2") (pin "E") (pinfunction "E1_E") (pintype "passive"))
      (node (ref "Q3") (pin "E") (pinfunction "E1_E") (pintype "passive"))
      (node (ref "R32") (pin "1") (pinfunction "1_1") (pintype "passive"))
      (node (ref "R5") (pin "2") (pinfunction "2_2") (pintype "passive"))
      (node (ref "R6") (pin "1") (pinfunction "1_1") (pintype "passive"))
      (node (ref "S2") (pin "5") (pinfunction "COMMON_5") (pintype "bidirectional"))
      (node (ref "SV3") (pin "1") (pinfunction "1_1") (pintype "passive"))
      (node (ref "SV5") (pin "12") (pinfunction "12_12") (pintype "passive"))
      (node (ref "SV5") (pin "9") (pinfunction "9_9") (pintype "passive"))
      (node (ref "SV7") (pin "12") (pinfunction "12_12") (pintype "passive"))
      (node (ref "SV7") (pin "9") (pinfunction "9_9") (pintype "passive"))
      (node (ref "U$1") (pin "7") (pinfunction "7_7") (pintype "passive"))
      (node (ref "U$2") (pin "GND0") (pinfunction "GND0_GND0") (pintype "bidirectional"))
      (node (ref "U$2") (pin "GND1") (pinfunction "GND1_GND1") (pintype "bidirectional"))
      (node (ref "U1") (pin "2") (pinfunction "GND_2") (pintype "passive"))
      (node (ref "U2") (pin "2") (pinfunction "GND_2") (pintype "passive"))
      (node (ref "U3") (pin "2") (pinfunction "GND_2") (pintype "passive"))
      (node (ref "U4") (pin "2") (pinfunction "GND_2") (pintype "passive"))
      (node (ref "U5") (pin "2") (pinfunction "GND_2") (pintype "passive"))
      (node (ref "U6") (pin "2") (pinfunction "GND_2") (pintype "passive"))
      (node (ref "U7") (pin "2") (pinfunction "GND_2") (pintype "passive"))
      (node (ref "U8") (pin "2") (pinfunction "GND_2") (pintype "passive"))
    )
    (net (code "71") (name "Net-(CONLEFT-PadA1)") (class "Default")
      (node (ref "CONLEFT") (pin "A1") (pinfunction "A1_A1") (pintype "bidirectional"))
      (node (ref "SV2") (pin "3") (pinfunction "3_3") (pintype "passive"))
    )
    (net (code "72") (name "Net-(CONLEFT-PadA2)") (class "Default")
      (node (ref "CONLEFT") (pin "A2") (pinfunction "A2_A2") (pintype "bidirectional"))
      (node (ref "SV2") (pin "4") (pinfunction "4_4") (pintype "passive"))
    )
    (net (code "73") (name "Net-(CONLEFT-PadB1)") (class "Default")
      (node (ref "CONLEFT") (pin "B1") (pinfunction "B1_B1") (pintype "bidirectional"))
      (node (ref "SV2") (pin "2") (pinfunction "2_2") (pintype "passive"))
    )
    (net (code "74") (name "Net-(CONLEFT-PadB2)") (class "Default")
      (node (ref "CONLEFT") (pin "B2") (pinfunction "B2_B2") (pintype "bidirectional"))
      (node (ref "SV2") (pin "1") (pinfunction "1_1") (pintype "passive"))
    )
    (net (code "75") (name "Net-(D1-PadA)") (class "Default")
      (node (ref "D1") (pin "A") (pinfunction "A_A") (pintype "passive"))
      (node (ref "R1") (pin "2") (pinfunction "2_2") (pintype "passive"))
    )
    (net (code "76") (name "Net-(D3-PadA)") (class "Default")
      (node (ref "D3") (pin "A") (pinfunction "A_A") (pintype "passive"))
      (node (ref "R4") (pin "2") (pinfunction "2_2") (pintype "passive"))
    )
    (net (code "77") (name "Net-(D4-PadA)") (class "Default")
      (node (ref "D4") (pin "A") (pinfunction "A_A") (pintype "passive"))
      (node (ref "S3") (pin "3") (pinfunction "3_3") (pintype "bidirectional"))
      (node (ref "SJ1") (pin "1") (pinfunction "1_1") (pintype "passive"))
    )
    (net (code "78") (name "Net-(D5-PadA)") (class "Default")
      (node (ref "D5") (pin "A") (pinfunction "A_A") (pintype "passive"))
      (node (ref "R30") (pin "2") (pinfunction "2_2") (pintype "passive"))
    )
    (net (code "79") (name "Net-(D6-PadA)") (class "Default")
      (node (ref "D6") (pin "A") (pinfunction "A_A") (pintype "passive"))
      (node (ref "R28") (pin "2") (pinfunction "2_2") (pintype "passive"))
    )
    (net (code "80") (name "Net-(D7-PadC)") (class "Default")
      (node (ref "D7") (pin "C") (pinfunction "C_C") (pintype "passive"))
      (node (ref "JP23") (pin "4") (pinfunction "4_4") (pintype "passive"))
    )
    (net (code "81") (name "Net-(IC3-B)") (class "Default")
      (node (ref "IC3") (pin "4") (pinfunction "B_4") (pintype "bidirectional"))
      (node (ref "JP1") (pin "1") (pinfunction "1_1") (pintype "passive"))
      (node (ref "JP13") (pin "2") (pinfunction "2_2") (pintype "passive"))
      (node (ref "LED1") (pin "1") (pinfunction "DI_1") (pintype "input"))
    )
    (net (code "82") (name "Net-(IC4-AIN)") (class "Default")
      (node (ref "IC4") (pin "3") (pinfunction "AIN_3") (pintype "bidirectional"))
      (node (ref "R2") (pin "2") (pinfunction "2_2") (pintype "passive"))
      (node (ref "R5") (pin "1") (pinfunction "1_1") (pintype "passive"))
    )
    (net (code "83") (name "Net-(IRLED0-A)") (class "Default")
      (node (ref "IRLED0") (pin "1") (pinfunction "A_1") (pintype "passive"))
      (node (ref "R31") (pin "2") (pinfunction "2_2") (pintype "passive"))
    )
    (net (code "84") (name "Net-(IRLED1-A)") (class "Default")
      (node (ref "IRLED1") (pin "1") (pinfunction "A_1") (pintype "passive"))
      (node (ref "R8") (pin "2") (pinfunction "2_2") (pintype "passive"))
    )
    (net (code "85") (name "Net-(IRLED2-A)") (class "Default")
      (node (ref "IRLED2") (pin "1") (pinfunction "A_1") (pintype "passive"))
      (node (ref "R10") (pin "2") (pinfunction "2_2") (pintype "passive"))
    )
    (net (code "86") (name "Net-(IRLED3-A)") (class "Default")
      (node (ref "IRLED3") (pin "1") (pinfunction "A_1") (pintype "passive"))
      (node (ref "R12") (pin "2") (pinfunction "2_2") (pintype "passive"))
    )
    (net (code "87") (name "Net-(IRLED4-A)") (class "Default")
      (node (ref "IRLED4") (pin "1") (pinfunction "A_1") (pintype "passive"))
      (node (ref "R14") (pin "2") (pinfunction "2_2") (pintype "passive"))
    )
    (net (code "88") (name "Net-(IRLED5-A)") (class "Default")
      (node (ref "IRLED5") (pin "1") (pinfunction "A_1") (pintype "passive"))
      (node (ref "R16") (pin "2") (pinfunction "2_2") (pintype "passive"))
    )
    (net (code "89") (name "Net-(IRLED6-A)") (class "Default")
      (node (ref "IRLED6") (pin "1") (pinfunction "A_1") (pintype "passive"))
      (node (ref "R18") (pin "2") (pinfunction "2_2") (pintype "passive"))
    )
    (net (code "90") (name "Net-(IRLED7-A)") (class "Default")
      (node (ref "IRLED7") (pin "1") (pinfunction "A_1") (pintype "passive"))
      (node (ref "R20") (pin "2") (pinfunction "2_2") (pintype "passive"))
    )
    (net (code "91") (name "Net-(IRLED8-A)") (class "Default")
      (node (ref "IRLED8") (pin "1") (pinfunction "A_1") (pintype "passive"))
      (node (ref "R22") (pin "2") (pinfunction "2_2") (pintype "passive"))
    )
    (net (code "92") (name "Net-(IRLED9-A)") (class "Default")
      (node (ref "IRLED9") (pin "1") (pinfunction "A_1") (pintype "passive"))
      (node (ref "R24") (pin "2") (pinfunction "2_2") (pintype "passive"))
    )
    (net (code "93") (name "Net-(IRLED10-A)") (class "Default")
      (node (ref "IRLED10") (pin "1") (pinfunction "A_1") (pintype "passive"))
      (node (ref "R26") (pin "2") (pinfunction "2_2") (pintype "passive"))
    )
    (net (code "94") (name "Net-(J3-Pad2)") (class "Default")
      (node (ref "J3") (pin "2") (pinfunction "2_2") (pintype "passive"))
      (node (ref "S3") (pin "2") (pinfunction "2_2") (pintype "bidirectional"))
    )
    (net (code "95") (name "Net-(JP14-Pad1)") (class "Default")
      (node (ref "JP14") (pin "1") (pinfunction "1_1") (pintype "passive"))
      (node (ref "JP15") (pin "2") (pinfunction "2_2") (pintype "passive"))
      (node (ref "S5") (pin "2") (pinfunction "2_2") (pintype "bidirectional"))
    )
    (net (code "96") (name "Net-(JP14-Pad2)") (class "Default")
      (node (ref "JP14") (pin "2") (pinfunction "2_2") (pintype "passive"))
      (node (ref "S6") (pin "1") (pinfunction "1_1") (pintype "bidirectional"))
    )
    (net (code "97") (name "Net-(LED1-DO)") (class "Default")
      (node (ref "JP1") (pin "2") (pinfunction "2_2") (pintype "passive"))
      (node (ref "JP2") (pin "1") (pinfunction "1_1") (pintype "passive"))
      (node (ref "LED1") (pin "3") (pinfunction "DO_3") (pintype "output"))
      (node (ref "LED2") (pin "1") (pinfunction "DI_1") (pintype "input"))
    )
    (net (code "98") (name "Net-(LED1-VDD)") (class "Default")
      (node (ref "C1") (pin "1") (pinfunction "1_1") (pintype "passive"))
      (node (ref "C2") (pin "1") (pinfunction "1_1") (pintype "passive"))
      (node (ref "C3") (pin "1") (pinfunction "1_1") (pintype "passive"))
      (node (ref "C4") (pin "1") (pinfunction "1_1") (pintype "passive"))
      (node (ref "C5") (pin "1") (pinfunction "1_1") (pintype "passive"))
      (node (ref "C6") (pin "1") (pinfunction "1_1") (pintype "passive"))
      (node (ref "C7") (pin "1") (pinfunction "1_1") (pintype "passive"))
      (node (ref "C8") (pin "1") (pinfunction "1_1") (pintype "passive"))
      (node (ref "C9") (pin "1") (pinfunction "1_1") (pintype "passive"))
      (node (ref "JP9") (pin "1") (pinfunction "1_1") (pintype "passive"))
      (node (ref "LED1") (pin "2") (pinfunction "VDD_2") (pintype "power_in"))
      (node (ref "LED2") (pin "2") (pinfunction "VDD_2") (pintype "power_in"))
      (node (ref "LED3") (pin "2") (pinfunction "VDD_2") (pintype "power_in"))
      (node (ref "LED4") (pin "2") (pinfunction "VDD_2") (pintype "power_in"))
      (node (ref "LED5") (pin "2") (pinfunction "VDD_2") (pintype "power_in"))
      (node (ref "LED6") (pin "2") (pinfunction "VDD_2") (pintype "power_in"))
      (node (ref "LED7") (pin "2") (pinfunction "VDD_2") (pintype "power_in"))
      (node (ref "LED8") (pin "2") (pinfunction "VDD_2") (pintype "power_in"))
      (node (ref "LED9") (pin "2") (pinfunction "VDD_2") (pintype "power_in"))
    )
    (net (code "99") (name "Net-(LED2-DO)") (class "Default")
      (node (ref "JP2") (pin "2") (pinfunction "2_2") (pintype "passive"))
      (node (ref "JP3") (pin "1") (pinfunction "1_1") (pintype "passive"))
      (node (ref "LED2") (pin "3") (pinfunction "DO_3") (pintype "output"))
      (node (ref "LED3") (pin "1") (pinfunction "DI_1") (pintype "input"))
    )
    (net (code "100") (name "Net-(LED3-DO)") (class "Default")
      (node (ref "JP3") (pin "2") (pinfunction "2_2") (pintype "passive"))
      (node (ref "JP4") (pin "1") (pinfunction "1_1") (pintype "passive"))
      (node (ref "LED3") (pin "3") (pinfunction "DO_3") (pintype "output"))
      (node (ref "LED4") (pin "1") (pinfunction "DI_1") (pintype "input"))
    )
    (net (code "101") (name "Net-(LED4-DO)") (class "Default")
      (node (ref "JP4") (pin "2") (pinfunction "2_2") (pintype "passive"))
      (node (ref "JP5") (pin "1") (pinfunction "1_1") (pintype "passive"))
      (node (ref "LED4") (pin "3") (pinfunction "DO_3") (pintype "output"))
      (node (ref "LED5") (pin "1") (pinfunction "DI_1") (pintype "input"))
    )
    (net (code "102") (name "Net-(LED5-DO)") (class "Default")
      (node (ref "JP5") (pin "2") (pinfunction "2_2") (pintype "passive"))
      (node (ref "JP6") (pin "1") (pinfunction "1_1") (pintype "passive"))
      (node (ref "LED5") (pin "3") (pinfunction "DO_3") (pintype "output"))
      (node (ref "LED6") (pin "1") (pinfunction "DI_1") (pintype "input"))
    )
    (net (code "103") (name "Net-(LED6-DO)") (class "Default")
      (node (ref "JP6") (pin "2") (pinfunction "2_2") (pintype "passive"))
      (node (ref "JP7") (pin "1") (pinfunction "1_1") (pintype "passive"))
      (node (ref "LED6") (pin "3") (pinfunction "DO_3") (pintype "output"))
      (node (ref "LED7") (pin "1") (pinfunction "DI_1") (pintype "input"))
    )
    (net (code "104") (name "Net-(LED7-DO)") (class "Default")
      (node (ref "JP7") (pin "2") (pinfunction "2_2") (pintype "passive"))
      (node (ref "JP8") (pin "1") (pinfunction "1_1") (pintype "passive"))
      (node (ref "LED7") (pin "3") (pinfunction "DO_3") (pintype "output"))
      (node (ref "LED8") (pin "1") (pinfunction "DI_1") (pintype "input"))
    )
    (net (code "105") (name "Net-(LED8-DO)") (class "Default")
      (node (ref "JP8") (pin "2") (pinfunction "2_2") (pintype "passive"))
      (node (ref "LED8") (pin "3") (pinfunction "DO_3") (pintype "output"))
      (node (ref "LED9") (pin "1") (pinfunction "DI_1") (pintype "input"))
    )
    (net (code "106") (name "Net-(LS1-1)") (class "Default")
      (node (ref "LS1") (pin "+") (pinfunction "1_+") (pintype "passive"))
      (node (ref "Q1") (pin "2") (pinfunction "E_2") (pintype "bidirectional"))
    )
    (net (code "107") (name "Net-(Q1-B)") (class "Default")
      (node (ref "Q1") (pin "1") (pinfunction "B_1") (pintype "bidirectional"))
      (node (ref "R3") (pin "1") (pinfunction "1_1") (pintype "passive"))
    )
    (net (code "108") (name "Net-(SV1-Pad1)") (class "Default")
      (node (ref "SV1") (pin "1") (pinfunction "1_1") (pintype "passive"))
      (node (ref "U$2") (pin "B2") (pinfunction "B2_B2") (pintype "bidirectional"))
    )
    (net (code "109") (name "Net-(SV1-Pad2)") (class "Default")
      (node (ref "SV1") (pin "2") (pinfunction "2_2") (pintype "passive"))
      (node (ref "U$2") (pin "B1") (pinfunction "B1_B1") (pintype "bidirectional"))
    )
    (net (code "110") (name "Net-(SV1-Pad3)") (class "Default")
      (node (ref "SV1") (pin "3") (pinfunction "3_3") (pintype "passive"))
      (node (ref "U$2") (pin "A1") (pinfunction "A1_A1") (pintype "bidirectional"))
    )
    (net (code "111") (name "Net-(SV1-Pad4)") (class "Default")
      (node (ref "SV1") (pin "4") (pinfunction "4_4") (pintype "passive"))
      (node (ref "U$2") (pin "A2") (pinfunction "A2_A2") (pintype "bidirectional"))
    )
    (net (code "112") (name "PTB18*") (class "Default")
      (node (ref "J8") (pin "15") (pinfunction "15_15") (pintype "passive"))
      (node (ref "S2") (pin "4") (pinfunction "B_4") (pintype "bidirectional"))
    )
    (net (code "113") (name "PTB19*") (class "Default")
      (node (ref "J8") (pin "13") (pinfunction "13_13") (pintype "passive"))
      (node (ref "S2") (pin "6") (pinfunction "D_6") (pintype "bidirectional"))
    )
    (net (code "114") (name "PTC0*") (class "Default")
      (node (ref "J8") (pin "5") (pinfunction "5_5") (pintype "passive"))
      (node (ref "S2") (pin "1") (pinfunction "A_1") (pintype "bidirectional"))
    )
    (net (code "115") (name "PTC1") (class "Default")
      (node (ref "R32") (pin "2") (pinfunction "2_2") (pintype "passive"))
      (node (ref "SV6") (pin "4") (pinfunction "4_4") (pintype "passive"))
      (node (ref "U7") (pin "6") (pinfunction "S_6") (pintype "input"))
      (node (ref "U8") (pin "6") (pinfunction "S_6") (pintype "input"))
    )
    (net (code "116") (name "PTC1*") (class "Default")
      (node (ref "J8") (pin "11") (pinfunction "11_11") (pintype "passive"))
      (node (ref "SV4") (pin "4") (pinfunction "4_4") (pintype "passive"))
    )
    (net (code "117") (name "PTC5") (class "Default")
      (node (ref "SV6") (pin "9") (pinfunction "9_9") (pintype "passive"))
      (node (ref "U$2") (pin "EN") (pinfunction "EN_EN") (pintype "bidirectional"))
    )
    (net (code "118") (name "PTC5*") (class "Default")
      (node (ref "J8") (pin "1") (pinfunction "1_1") (pintype "passive"))
      (node (ref "SV4") (pin "9") (pinfunction "9_9") (pintype "passive"))
    )
    (net (code "119") (name "PTC7") (class "Default")
      (node (ref "CONLEFT") (pin "EN") (pinfunction "EN_EN") (pintype "bidirectional"))
      (node (ref "SV6") (pin "7") (pinfunction "7_7") (pintype "passive"))
    )
    (net (code "120") (name "PTC7*") (class "Default")
      (node (ref "J8") (pin "3") (pinfunction "3_3") (pintype "passive"))
      (node (ref "SV4") (pin "7") (pinfunction "7_7") (pintype "passive"))
    )
    (net (code "121") (name "PTC8*") (class "Default")
      (node (ref "J8") (pin "9") (pinfunction "9_9") (pintype "passive"))
      (node (ref "S2") (pin "3") (pinfunction "C_3") (pintype "bidirectional"))
    )
    (net (code "122") (name "PTC9*") (class "Default")
      (node (ref "J8") (pin "7") (pinfunction "7_7") (pintype "passive"))
      (node (ref "S2") (pin "2") (pinfunction "CENTER_2") (pintype "bidirectional"))
    )
    (net (code "123") (name "PTE26") (class "Default")
      (node (ref "J1") (pin "1") (pinfunction "1_1") (pintype "passive"))
      (node (ref "SV7") (pin "10") (pinfunction "10_10") (pintype "passive"))
    )
    (net (code "124") (name "PTE26*") (class "Default")
      (node (ref "J7") (pin "1") (pinfunction "1_1") (pintype "passive"))
      (node (ref "SV5") (pin "10") (pinfunction "10_10") (pintype "passive"))
    )
    (net (code "125") (name "SCL") (class "Default")
      (node (ref "IC4") (pin "5") (pinfunction "SCL_5") (pintype "bidirectional"))
      (node (ref "JP11") (pin "9") (pinfunction "9_9") (pintype "passive"))
      (node (ref "JP27") (pin "2") (pinfunction "2_2") (pintype "passive"))
      (node (ref "SV3") (pin "3") (pinfunction "3_3") (pintype "passive"))
      (node (ref "SV7") (pin "7") (pinfunction "7_7") (pintype "passive"))
    )
    (net (code "126") (name "SCL*") (class "Default")
      (node (ref "SV5") (pin "7") (pinfunction "7_7") (pintype "passive"))
      (node (ref "U$1") (pin "10") (pinfunction "10_10") (pintype "passive"))
    )
    (net (code "127") (name "SCL_") (class "Default")
      (node (ref "JP10") (pin "8") (pinfunction "8_8") (pintype "passive"))
    )
    (net (code "128") (name "SDA") (class "Default")
      (node (ref "IC4") (pin "4") (pinfunction "SDA_4") (pintype "bidirectional"))
      (node (ref "JP11") (pin "8") (pinfunction "8_8") (pintype "passive"))
      (node (ref "JP27") (pin "1") (pinfunction "1_1") (pintype "passive"))
      (node (ref "SV3") (pin "4") (pinfunction "4_4") (pintype "passive"))
      (node (ref "SV7") (pin "5") (pinfunction "5_5") (pintype "passive"))
    )
    (net (code "129") (name "SDA*") (class "Default")
      (node (ref "SV5") (pin "5") (pinfunction "5_5") (pintype "passive"))
      (node (ref "U$1") (pin "9") (pinfunction "9_9") (pintype "passive"))
    )
    (net (code "130") (name "SDA_") (class "Default")
      (node (ref "JP10") (pin "9") (pinfunction "9_9") (pintype "passive"))
    )
    (net (code "131") (name "VIN") (class "Default")
      (node (ref "C10") (pin "1") (pinfunction "1_1") (pintype "passive"))
      (node (ref "C12") (pin "1") (pinfunction "1_1") (pintype "passive"))
      (node (ref "C14") (pin "2") (pinfunction "2_2") (pintype "bidirectional"))
      (node (ref "C15") (pin "2") (pinfunction "2_2") (pintype "bidirectional"))
      (node (ref "CONLEFT") (pin "VMOT") (pinfunction "VMOT_VMOT") (pintype "bidirectional"))
      (node (ref "D4") (pin "C") (pinfunction "C_C") (pintype "passive"))
      (node (ref "D7") (pin "A") (pinfunction "A_A") (pintype "passive"))
      (node (ref "IC1") (pin "3") (pinfunction "IN_3") (pintype "input"))
      (node (ref "IC2") (pin "3") (pinfunction "IN_3") (pintype "input"))
      (node (ref "JP11") (pin "4") (pinfunction "4_4") (pintype "passive"))
      (node (ref "R1") (pin "1") (pinfunction "1_1") (pintype "passive"))
      (node (ref "R2") (pin "1") (pinfunction "1_1") (pintype "passive"))
      (node (ref "SJ1") (pin "2") (pinfunction "2_2") (pintype "passive"))
      (node (ref "U$2") (pin "VMOT") (pinfunction "VMOT_VMOT") (pintype "bidirectional"))
    )
    (net (code "132") (name "VIN*") (class "Default")
      (node (ref "J5") (pin "8") (pinfunction "8_8") (pintype "passive"))
      (node (ref "JP21") (pin "4") (pinfunction "4_4") (pintype "passive"))
    )
    (net (code "133") (name "VIN_") (class "Default")
      (node (ref "JP10") (pin "13") (pinfunction "13_13") (pintype "passive"))
    )
    (net (code "134") (name "unconnected-(CONLEFT-(CONFIG)-PadCONFIG)") (class "Default")
      (node (ref "CONLEFT") (pin "CONFIG") (pinfunction "(CONFIG)_CONFIG") (pintype "bidirectional"))
    )
    (net (code "135") (name "unconnected-(CONLEFT-(VREF)-PadVREF)") (class "Default")
      (node (ref "CONLEFT") (pin "VREF") (pinfunction "(VREF)_VREF") (pintype "bidirectional"))
    )
    (net (code "136") (name "unconnected-(CONLEFT-PadFLT)") (class "Default")
      (node (ref "CONLEFT") (pin "FLT") (pinfunction "FLT_FLT") (pintype "bidirectional"))
    )
    (net (code "137") (name "unconnected-(J5-Pad1)") (class "Default")
      (node (ref "J5") (pin "1") (pinfunction "1_1") (pintype "passive"))
    )
    (net (code "138") (name "unconnected-(J5-Pad2)") (class "Default")
      (node (ref "J5") (pin "2") (pinfunction "2_2") (pintype "passive"))
    )
    (net (code "139") (name "unconnected-(J5-Pad3)") (class "Default")
      (node (ref "J5") (pin "3") (pinfunction "3_3") (pintype "passive"))
    )
    (net (code "140") (name "unconnected-(J5-Pad4)") (class "Default")
      (node (ref "J5") (pin "4") (pinfunction "4_4") (pintype "passive"))
    )
    (net (code "141") (name "unconnected-(J5-Pad5)") (class "Default")
      (node (ref "J5") (pin "5") (pinfunction "5_5") (pintype "passive"))
    )
    (net (code "142") (name "unconnected-(JP10-Pad12)") (class "Default")
      (node (ref "JP10") (pin "12") (pinfunction "12_12") (pintype "passive"))
    )
    (net (code "143") (name "unconnected-(JP11-Pad5)") (class "Default")
      (node (ref "JP11") (pin "5") (pinfunction "5_5") (pintype "passive"))
    )
    (net (code "144") (name "unconnected-(LED9-DO-Pad3)") (class "Default")
      (node (ref "LED9") (pin "3") (pinfunction "DO_3") (pintype "output"))
    )
    (net (code "145") (name "unconnected-(S2-Pad7)") (class "Default")
      (node (ref "S2") (pin "7") (pinfunction "7_7") (pintype "bidirectional"))
    )
    (net (code "146") (name "unconnected-(S2-Pad8)") (class "Default")
      (node (ref "S2") (pin "8") (pinfunction "8_8") (pintype "bidirectional"))
    )
    (net (code "147") (name "unconnected-(S3-Pad1)") (class "Default")
      (node (ref "S3") (pin "1") (pinfunction "1_1") (pintype "bidirectional"))
    )
    (net (code "148") (name "unconnected-(S5-Pad3)") (class "Default")
      (node (ref "S5") (pin "3") (pinfunction "3_3") (pintype "bidirectional"))
    )
    (net (code "149") (name "unconnected-(S6-Pad3)") (class "Default")
      (node (ref "S6") (pin "3") (pinfunction "3_3") (pintype "bidirectional"))
    )
    (net (code "150") (name "unconnected-(U$1-Pad8)") (class "Default")
      (node (ref "U$1") (pin "8") (pinfunction "8_8") (pintype "passive"))
    )
    (net (code "151") (name "unconnected-(U$2-(CONFIG)-PadCONFIG)") (class "Default")
      (node (ref "U$2") (pin "CONFIG") (pinfunction "(CONFIG)_CONFIG") (pintype "bidirectional"))
    )
    (net (code "152") (name "unconnected-(U$2-(VREF)-PadVREF)") (class "Default")
      (node (ref "U$2") (pin "VREF") (pinfunction "(VREF)_VREF") (pintype "bidirectional"))
    )
    (net (code "153") (name "unconnected-(U$2-PadFLT)") (class "Default")
      (node (ref "U$2") (pin "FLT") (pinfunction "FLT_FLT") (pintype "bidirectional"))
    )
  )
)
